# Mixer_Console_PCB.net
KiCad netlist of a schematic drawn in EAGLE
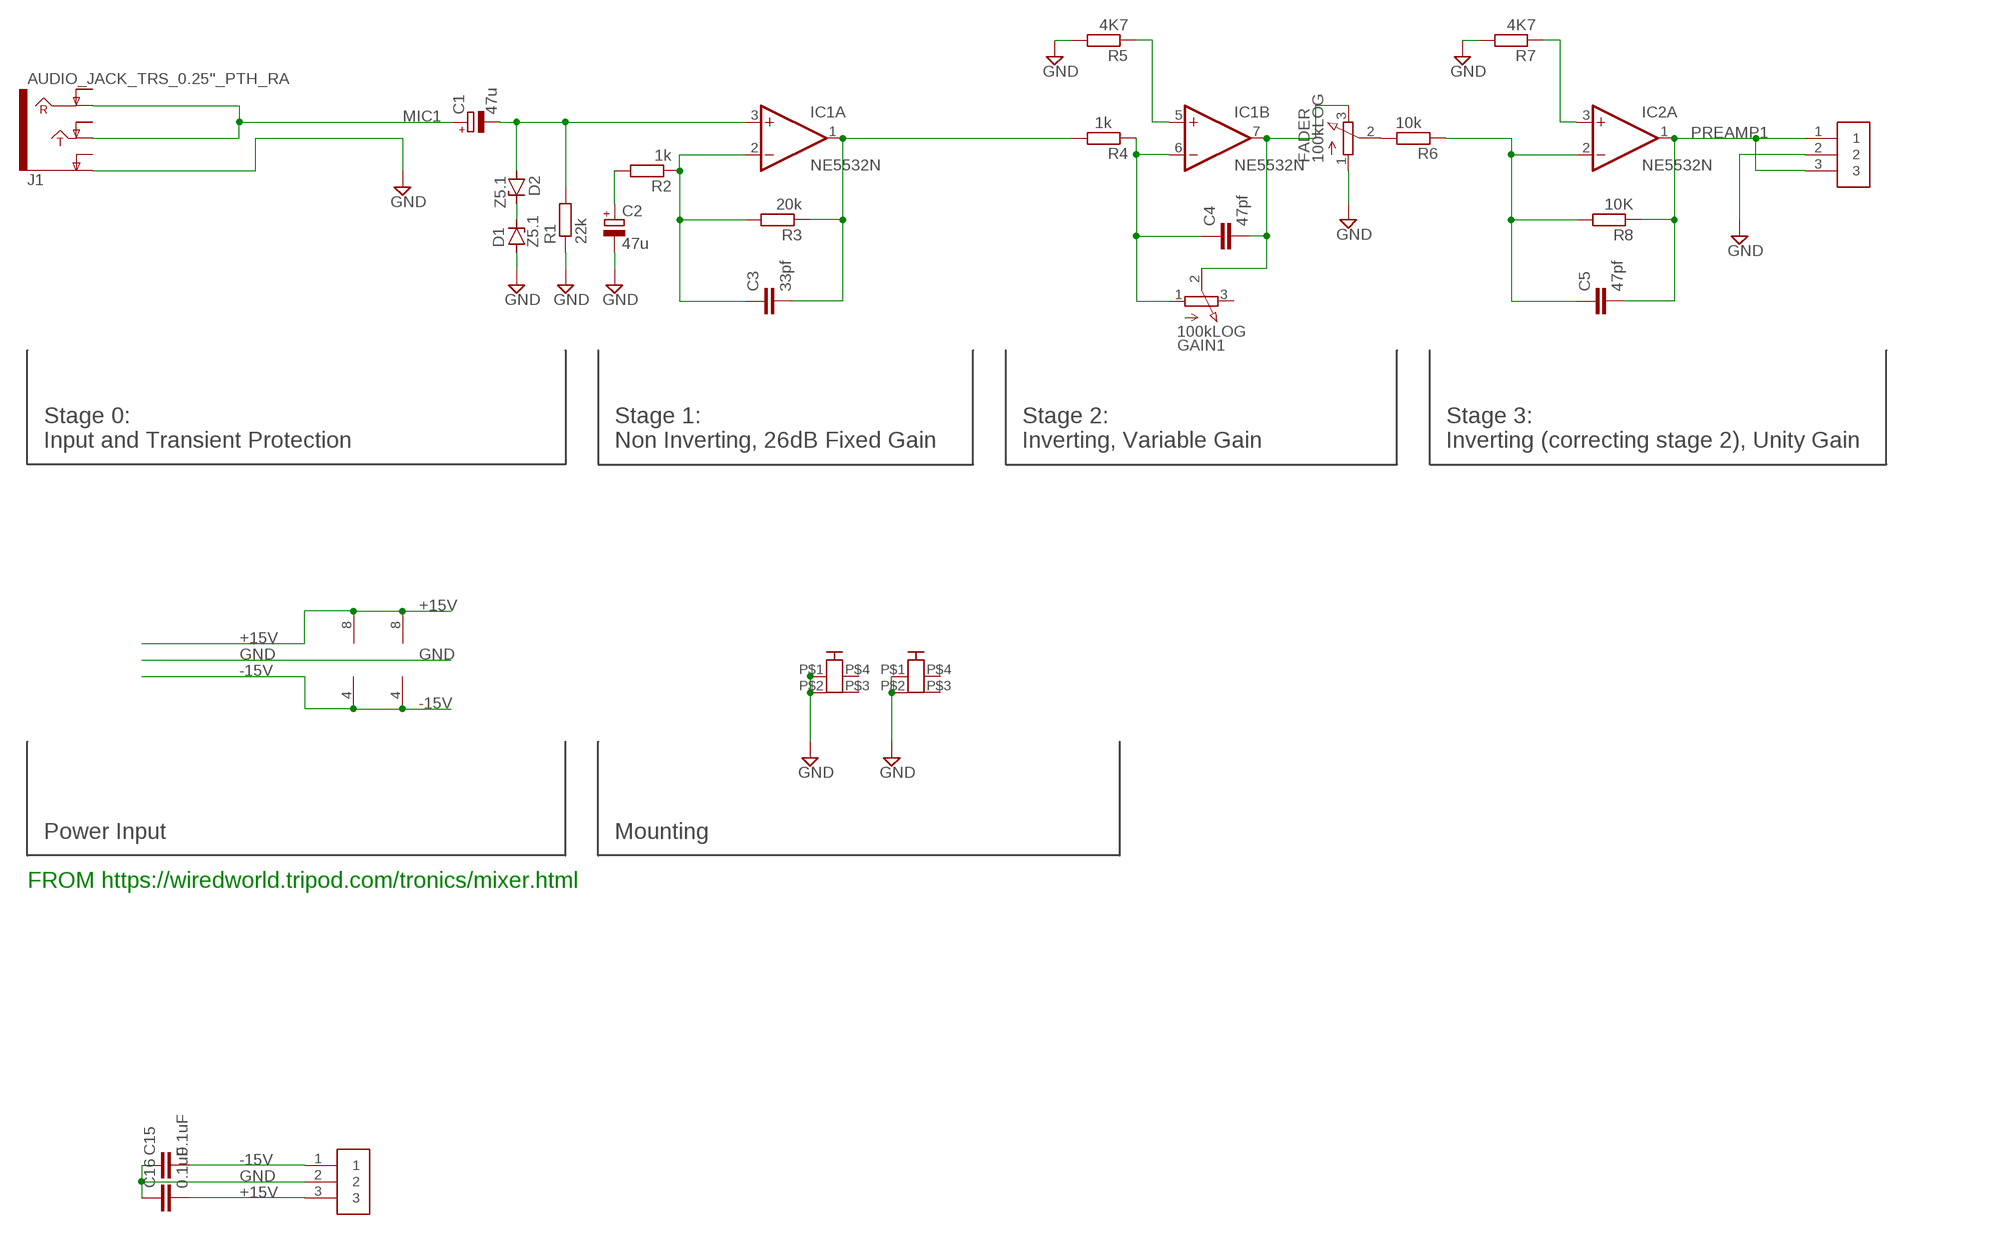
[diagram p0: schematic, sheet 1]
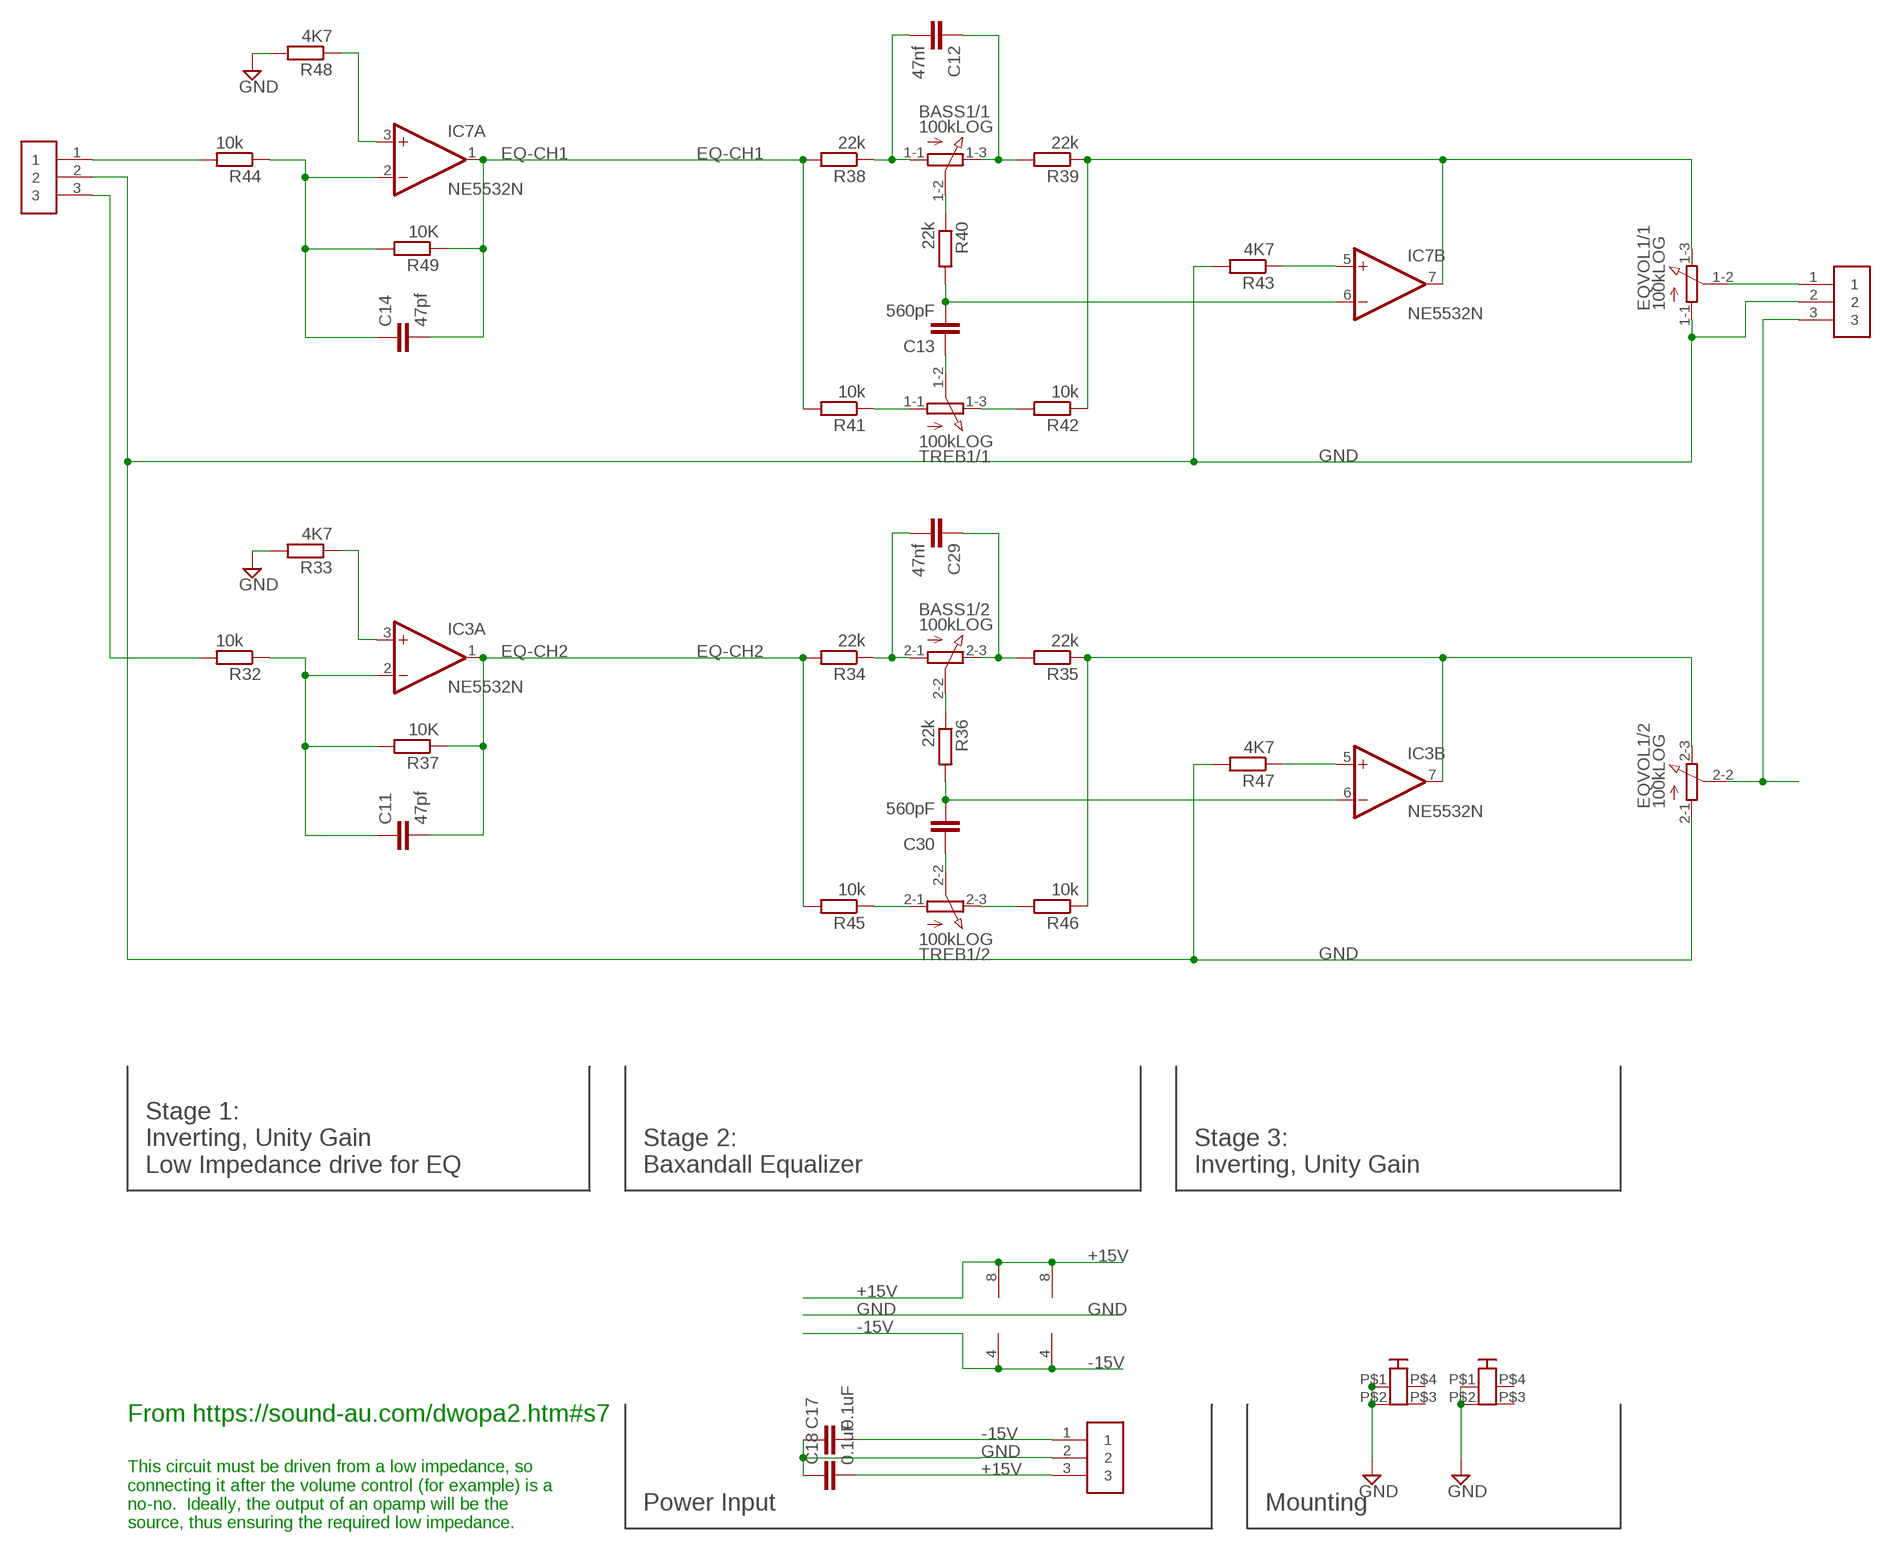
[diagram p1: schematic, sheet 2]
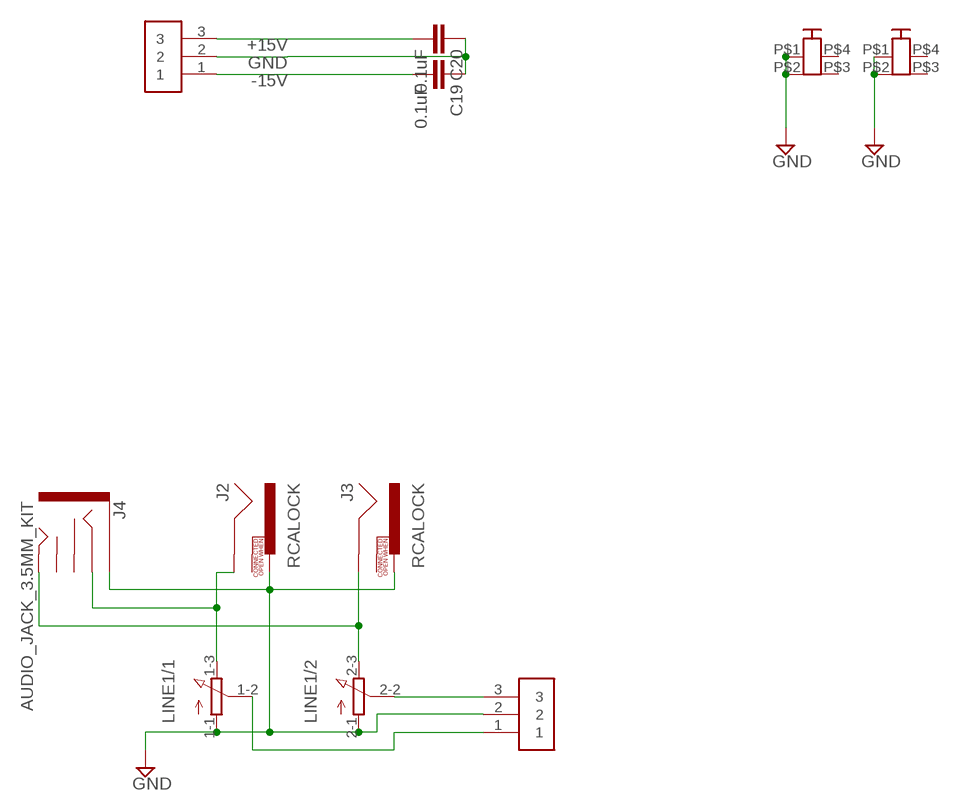
[diagram p2: schematic, sheet 3]
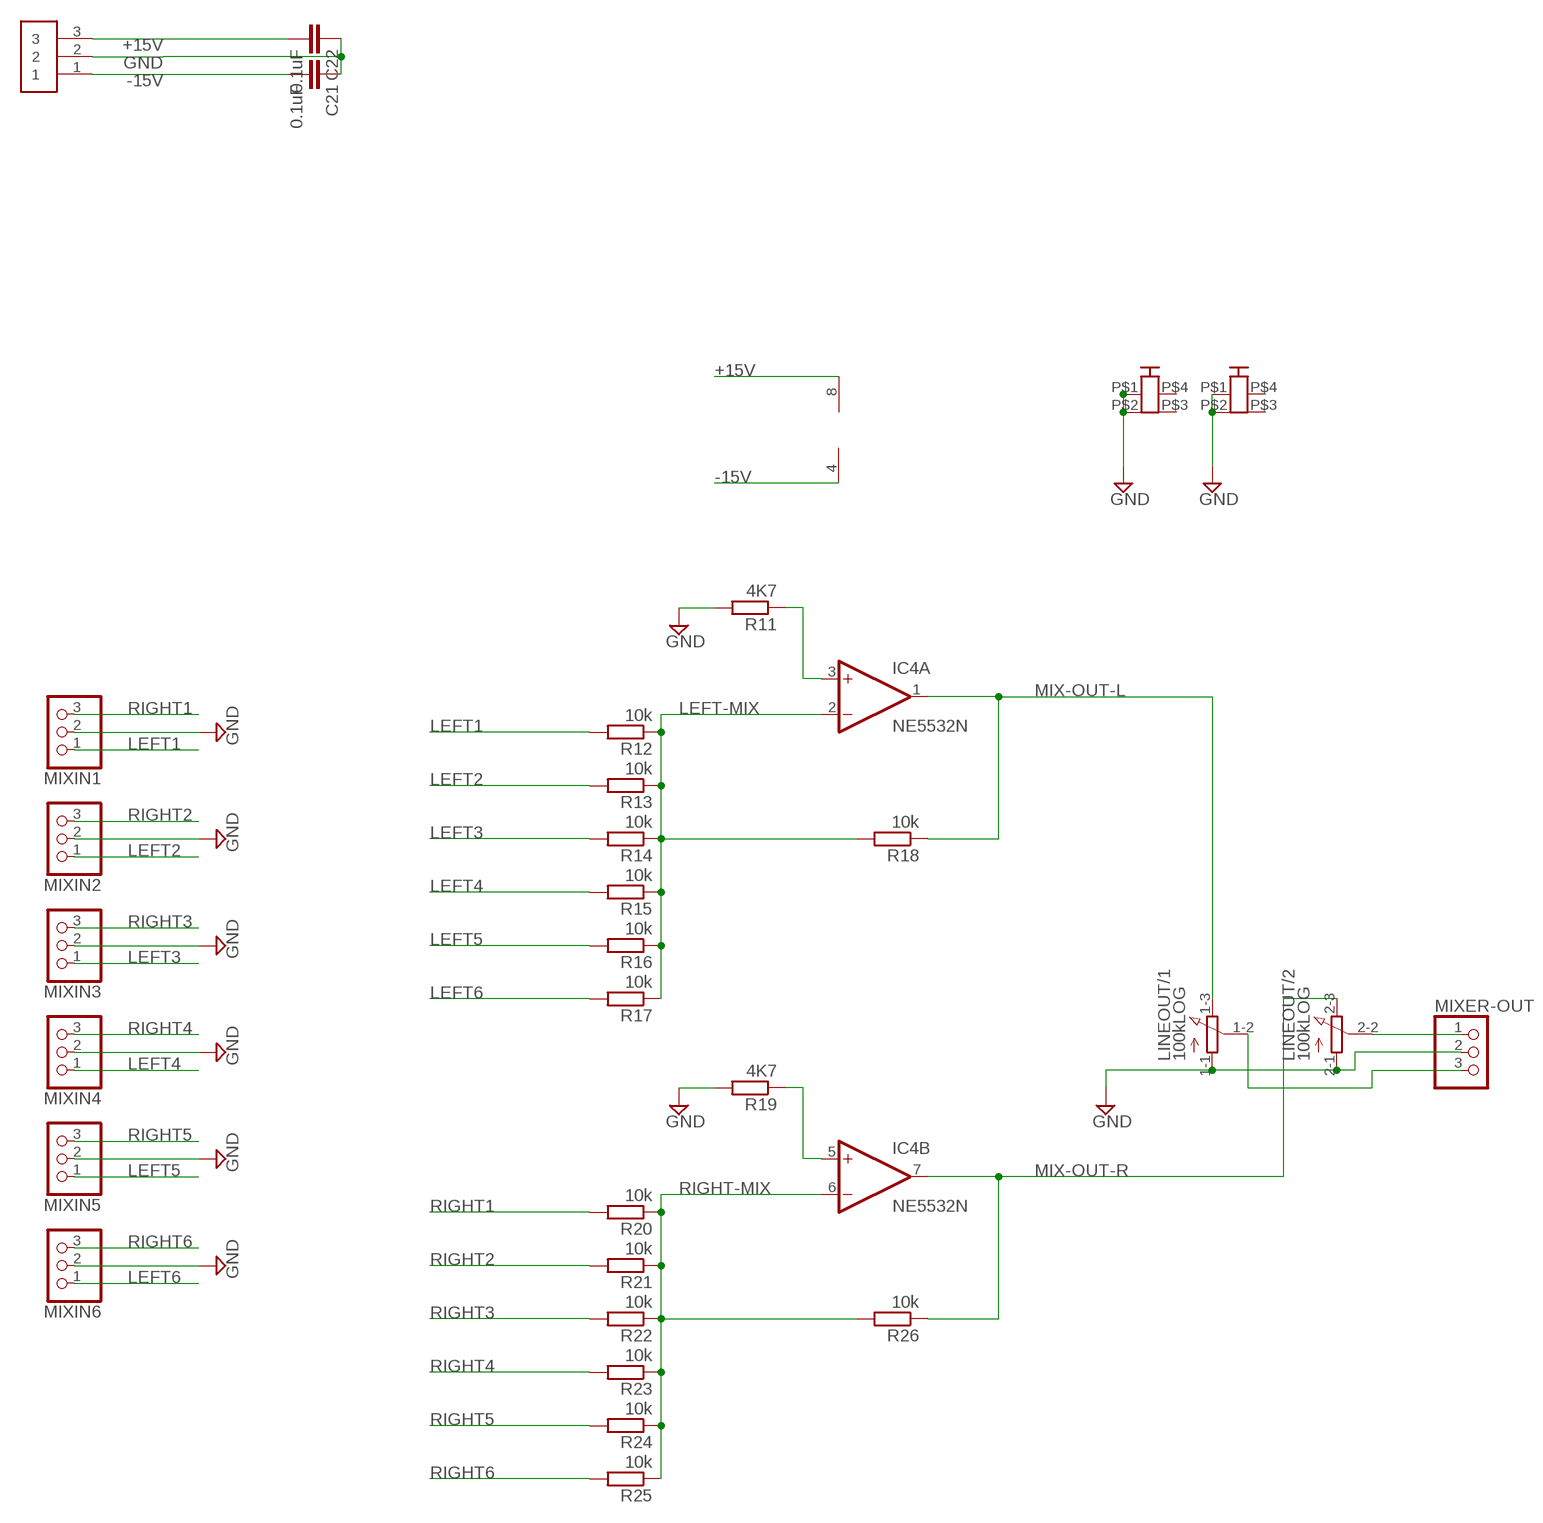
[diagram p3: schematic, sheet 4]
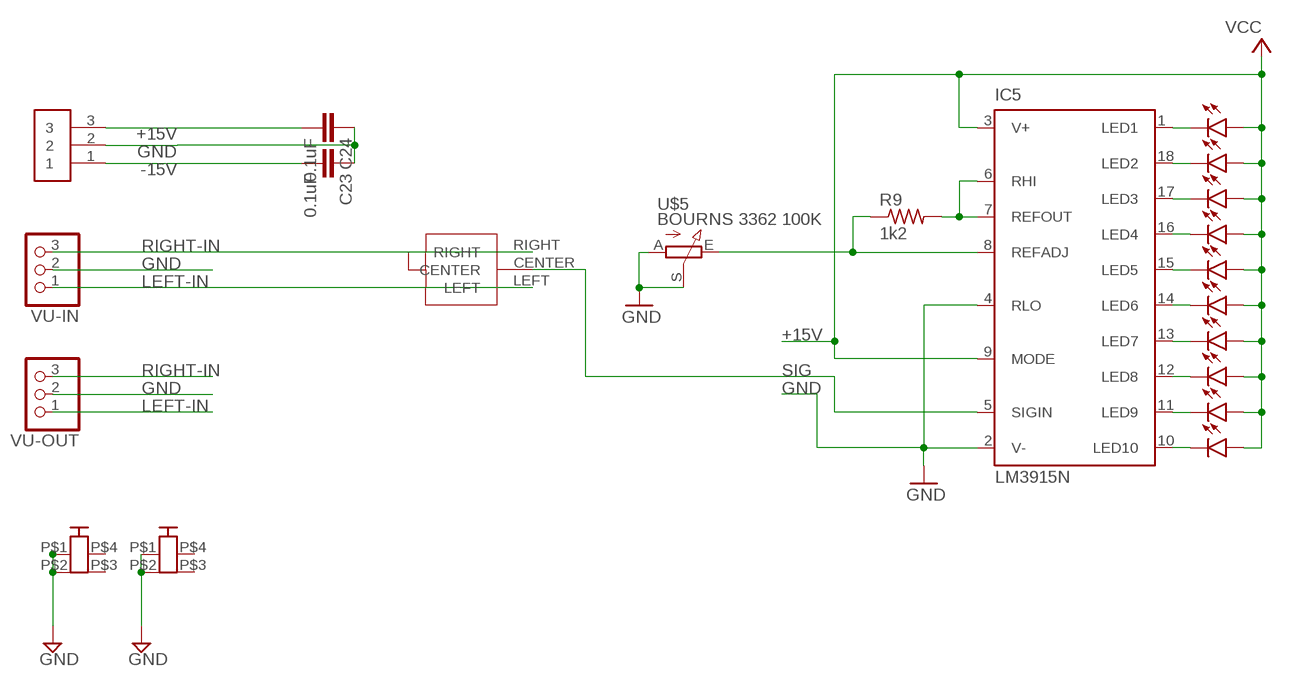
[diagram p4: schematic, sheet 5]
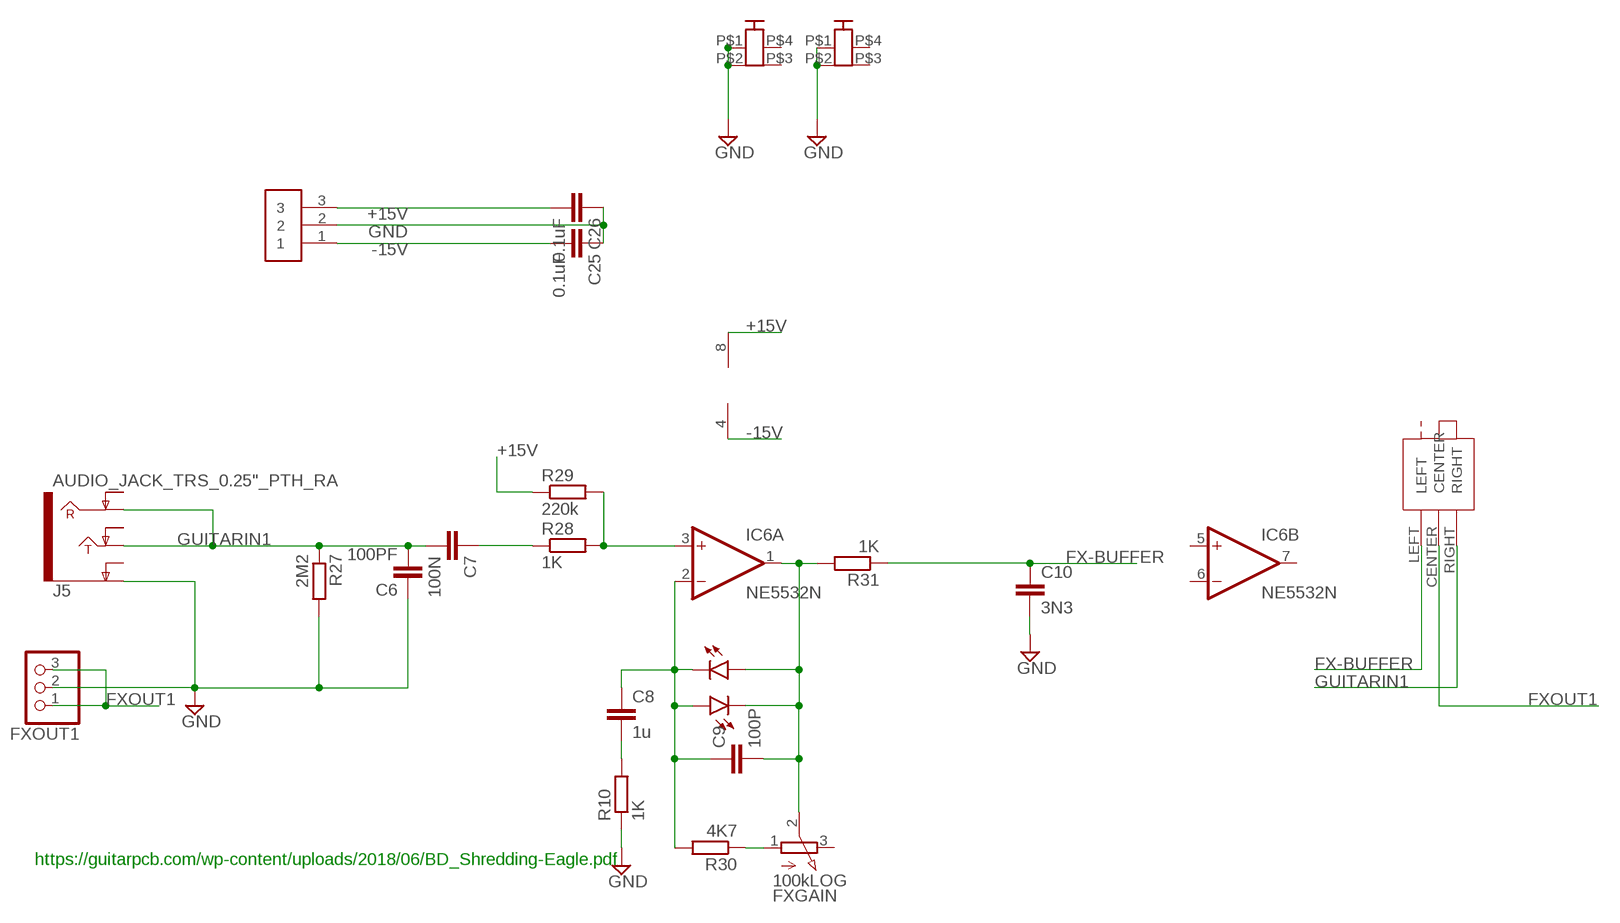
[diagram p5: schematic, sheet 6]

(export (version "E")
  (design (tool "Eeschema 10.0.6"))
  (components
    (comp (ref "BASS1")
      (value "100kLOG")
      (footprint "eagle-import:3RP_1610G")
      (fields (field (name "SPICEPREFIX") "J"))
      (libsource (lib "eagle-import") (part "3RP/1610G"))
    )
    (comp (ref "C11")
      (value "47pf")
      (footprint "eagle-import:C2.5-2")
      (libsource (lib "eagle-import") (part "C2.5/2"))
    )
    (comp (ref "C12")
      (value "47nf")
      (footprint "eagle-import:C2.5-2")
      (libsource (lib "eagle-import") (part "C2.5/2"))
    )
    (comp (ref "C13")
      (value "560pF")
      (footprint "eagle-import:C2.5-2")
      (libsource (lib "eagle-import") (part "C2.5/2"))
    )
    (comp (ref "C14")
      (value "47pf")
      (footprint "eagle-import:C2.5-2")
      (libsource (lib "eagle-import") (part "C2.5/2"))
    )
    (comp (ref "C17")
      (value "0.1uF")
      (footprint "eagle-import:C2.5-2")
      (libsource (lib "eagle-import") (part "C2.5/2"))
    )
    (comp (ref "C18")
      (value "0.1uF")
      (footprint "eagle-import:C2.5-2")
      (libsource (lib "eagle-import") (part "C2.5/2"))
    )
    (comp (ref "C29")
      (value "47nf")
      (footprint "eagle-import:C2.5-2")
      (libsource (lib "eagle-import") (part "C2.5/2"))
    )
    (comp (ref "C30")
      (value "560pF")
      (footprint "eagle-import:C2.5-2")
      (libsource (lib "eagle-import") (part "C2.5/2"))
    )
    (comp (ref "CON1")
      (value "PCB-2M3")
      (footprint "eagle-import:PCB2-M3")
      (libsource (lib "eagle-import") (part "PCB-2M3"))
    )
    (comp (ref "CON2")
      (value "PCB-2M3")
      (footprint "eagle-import:PCB2-M3")
      (libsource (lib "eagle-import") (part "PCB-2M3"))
    )
    (comp (ref "EQIN")
      (value "Phoenix Pluggable 3.81mm 3 way")
      (footprint "eagle-import:3.81MM-3WAY-PLUGGABLE-SCREW")
      (libsource (lib "eagle-import") (part "CONNECTOR-M3"))
    )
    (comp (ref "EQOUT")
      (value "Phoenix Pluggable 3.81mm 3 way")
      (footprint "eagle-import:3.81MM-3WAY-PLUGGABLE-SCREW")
      (libsource (lib "eagle-import") (part "CONNECTOR-M3"))
    )
    (comp (ref "EQVOL1")
      (value "100kLOG")
      (footprint "eagle-import:3RP_1610G")
      (fields (field (name "SPICEPREFIX") "J"))
      (libsource (lib "eagle-import") (part "3RP/1610G"))
    )
    (comp (ref "IC3")
      (value "NE5532N")
      (footprint "eagle-import:DIL08")
      (libsource (lib "eagle-import") (part "NE5532N"))
    )
    (comp (ref "IC7")
      (value "NE5532N")
      (footprint "eagle-import:DIL08")
      (libsource (lib "eagle-import") (part "NE5532N"))
    )
    (comp (ref "PWRIN1")
      (value "Phoenix Pluggable 3.81mm 3 way")
      (footprint "eagle-import:3.81MM-3WAY-PLUGGABLE-SCREW")
      (libsource (lib "eagle-import") (part "CONNECTOR-M3"))
    )
    (comp (ref "R32")
      (value "10k")
      (footprint "eagle-import:0204_7")
      (libsource (lib "eagle-import") (part "R-EU_0204/7"))
    )
    (comp (ref "R33")
      (value "4K7")
      (footprint "eagle-import:0204_7")
      (libsource (lib "eagle-import") (part "R-EU_0204/7"))
    )
    (comp (ref "R34")
      (value "22k")
      (footprint "eagle-import:0204_7")
      (libsource (lib "eagle-import") (part "R-EU_0204/7"))
    )
    (comp (ref "R35")
      (value "22k")
      (footprint "eagle-import:0204_7")
      (libsource (lib "eagle-import") (part "R-EU_0204/7"))
    )
    (comp (ref "R36")
      (value "22k")
      (footprint "eagle-import:0204_7")
      (libsource (lib "eagle-import") (part "R-EU_0204/7"))
    )
    (comp (ref "R37")
      (value "10K")
      (footprint "eagle-import:0204_7")
      (libsource (lib "eagle-import") (part "R-EU_0204/7"))
    )
    (comp (ref "R38")
      (value "22k")
      (footprint "eagle-import:0204_7")
      (libsource (lib "eagle-import") (part "R-EU_0204/7"))
    )
    (comp (ref "R39")
      (value "22k")
      (footprint "eagle-import:0204_7")
      (libsource (lib "eagle-import") (part "R-EU_0204/7"))
    )
    (comp (ref "R40")
      (value "22k")
      (footprint "eagle-import:0204_7")
      (libsource (lib "eagle-import") (part "R-EU_0204/7"))
    )
    (comp (ref "R41")
      (value "10k")
      (footprint "eagle-import:0204_7")
      (libsource (lib "eagle-import") (part "R-EU_0204/7"))
    )
    (comp (ref "R42")
      (value "10k")
      (footprint "eagle-import:0204_7")
      (libsource (lib "eagle-import") (part "R-EU_0204/7"))
    )
    (comp (ref "R43")
      (value "4K7")
      (footprint "eagle-import:0204_7")
      (libsource (lib "eagle-import") (part "R-EU_0204/7"))
    )
    (comp (ref "R44")
      (value "10k")
      (footprint "eagle-import:0204_7")
      (libsource (lib "eagle-import") (part "R-EU_0204/7"))
    )
    (comp (ref "R45")
      (value "10k")
      (footprint "eagle-import:0204_7")
      (libsource (lib "eagle-import") (part "R-EU_0204/7"))
    )
    (comp (ref "R46")
      (value "10k")
      (footprint "eagle-import:0204_7")
      (libsource (lib "eagle-import") (part "R-EU_0204/7"))
    )
    (comp (ref "R47")
      (value "4K7")
      (footprint "eagle-import:0204_7")
      (libsource (lib "eagle-import") (part "R-EU_0204/7"))
    )
    (comp (ref "R48")
      (value "4K7")
      (footprint "eagle-import:0204_7")
      (libsource (lib "eagle-import") (part "R-EU_0204/7"))
    )
    (comp (ref "R49")
      (value "10K")
      (footprint "eagle-import:0204_7")
      (libsource (lib "eagle-import") (part "R-EU_0204/7"))
    )
    (comp (ref "TREB1")
      (value "100kLOG")
      (footprint "eagle-import:3RP_1610G")
      (fields (field (name "SPICEPREFIX") "J"))
      (libsource (lib "eagle-import") (part "3RP/1610G"))
    )
    (comp (ref "C6")
      (value "100PF")
      (footprint "eagle-import:C2.5-2")
      (libsource (lib "eagle-import") (part "C2.5/2"))
    )
    (comp (ref "C7")
      (value "100N")
      (footprint "eagle-import:C2.5-2")
      (libsource (lib "eagle-import") (part "C2.5/2"))
    )
    (comp (ref "C8")
      (value "1u")
      (footprint "eagle-import:C2.5-2")
      (libsource (lib "eagle-import") (part "C2.5/2"))
    )
    (comp (ref "C9")
      (value "100P")
      (footprint "eagle-import:C2.5-2")
      (libsource (lib "eagle-import") (part "C2.5/2"))
    )
    (comp (ref "C10")
      (value "3N3")
      (footprint "eagle-import:C2.5-2")
      (libsource (lib "eagle-import") (part "C2.5/2"))
    )
    (comp (ref "C25")
      (value "0.1uF")
      (footprint "eagle-import:C2.5-2")
      (libsource (lib "eagle-import") (part "C2.5/2"))
    )
    (comp (ref "C26")
      (value "0.1uF")
      (footprint "eagle-import:C2.5-2")
      (libsource (lib "eagle-import") (part "C2.5/2"))
    )
    (comp (ref "CON9")
      (value "PCB-2M3")
      (footprint "eagle-import:PCB2-M3")
      (libsource (lib "eagle-import") (part "PCB-2M3"))
    )
    (comp (ref "CON10")
      (value "PCB-2M3")
      (footprint "eagle-import:PCB2-M3")
      (libsource (lib "eagle-import") (part "PCB-2M3"))
    )
    (comp (ref "FXGAIN")
      (value "100kLOG")
      (footprint "eagle-import:3RP_1610N")
      (libsource (lib "eagle-import") (part "3RP/1610N"))
    )
    (comp (ref "FXOUT1")
      (value "PINHD-1X3/90")
      (footprint "eagle-import:1X03_90")
      (libsource (lib "eagle-import") (part "PINHD-1X3/90"))
    )
    (comp (ref "IC6")
      (value "NE5532N")
      (footprint "eagle-import:DIL08")
      (libsource (lib "eagle-import") (part "NE5532N"))
    )
    (comp (ref "J5")
      (value "AUDIO_JACK_TRS_0.25\"_PTH_RA")
      (footprint "eagle-import:AUDIO_JACK_0.25__TRS_PTH_RA")
      (libsource (lib "eagle-import") (part "AUDIO_JACK_TRS_0.25{dblquote}_PTH_RA"))
    )
    (comp (ref "LED11")
      (value "LED3MM")
      (footprint "eagle-import:LED3MM")
      (libsource (lib "eagle-import") (part "LED3MM"))
    )
    (comp (ref "LED12")
      (value "LED3MM")
      (footprint "eagle-import:LED3MM")
      (libsource (lib "eagle-import") (part "LED3MM"))
    )
    (comp (ref "PWRIN5")
      (value "Phoenix Pluggable 3.81mm 3 way")
      (footprint "eagle-import:3.81MM-3WAY-PLUGGABLE-SCREW")
      (libsource (lib "eagle-import") (part "CONNECTOR-M3"))
    )
    (comp (ref "R10")
      (value "1K")
      (footprint "eagle-import:0204_7")
      (libsource (lib "eagle-import") (part "R-EU_0204/7"))
    )
    (comp (ref "R27")
      (value "2M2")
      (footprint "eagle-import:0204_7")
      (libsource (lib "eagle-import") (part "R-EU_0204/7"))
    )
    (comp (ref "R28")
      (value "1K")
      (footprint "eagle-import:0204_7")
      (libsource (lib "eagle-import") (part "R-EU_0204/7"))
    )
    (comp (ref "R29")
      (value "220k")
      (footprint "eagle-import:0204_7")
      (libsource (lib "eagle-import") (part "R-EU_0204/7"))
    )
    (comp (ref "R30")
      (value "4K7")
      (footprint "eagle-import:0204_7")
      (libsource (lib "eagle-import") (part "R-EU_0204/7"))
    )
    (comp (ref "R31")
      (value "1K")
      (footprint "eagle-import:0204_7")
      (libsource (lib "eagle-import") (part "R-EU_0204/7"))
    )
    (comp (ref "U$1")
      (value "XKBENTERPRISESS-12D11G5R")
      (footprint "eagle-import:XKBENTERPRISESS-12D11G5R")
      (libsource (lib "eagle-import") (part "XKBENTERPRISESS-12D11G5R"))
    )
    (comp (ref "C1")
      (value "47u")
      (footprint "eagle-import:E5-6")
      (libsource (lib "eagle-import") (part "CPOL-EUE5-6"))
    )
    (comp (ref "C2")
      (value "47u")
      (footprint "eagle-import:E5-6")
      (libsource (lib "eagle-import") (part "CPOL-EUE5-6"))
    )
    (comp (ref "C3")
      (value "33pf")
      (footprint "eagle-import:C2.5-2")
      (libsource (lib "eagle-import") (part "C2.5/2"))
    )
    (comp (ref "C4")
      (value "47pf")
      (footprint "eagle-import:C2.5-2")
      (libsource (lib "eagle-import") (part "C2.5/2"))
    )
    (comp (ref "C5")
      (value "47pf")
      (footprint "eagle-import:C2.5-2")
      (libsource (lib "eagle-import") (part "C2.5/2"))
    )
    (comp (ref "C15")
      (value "0.1uF")
      (footprint "eagle-import:C2.5-2")
      (libsource (lib "eagle-import") (part "C2.5/2"))
    )
    (comp (ref "C16")
      (value "0.1uF")
      (footprint "eagle-import:C2.5-2")
      (libsource (lib "eagle-import") (part "C2.5/2"))
    )
    (comp (ref "CON11")
      (value "PCB-2M3")
      (footprint "eagle-import:PCB2-M3")
      (libsource (lib "eagle-import") (part "PCB-2M3"))
    )
    (comp (ref "CON12")
      (value "PCB-2M3")
      (footprint "eagle-import:PCB2-M3")
      (libsource (lib "eagle-import") (part "PCB-2M3"))
    )
    (comp (ref "D1")
      (value "Z5.1")
      (footprint "eagle-import:DO34Z7")
      (libsource (lib "eagle-import") (part "ZENER-DIODEDO34-7"))
    )
    (comp (ref "D2")
      (value "Z5.1")
      (footprint "eagle-import:DO34Z7")
      (libsource (lib "eagle-import") (part "ZENER-DIODEDO34-7"))
    )
    (comp (ref "FADER")
      (value "100kLOG")
      (footprint "eagle-import:3RP_1610N")
      (libsource (lib "eagle-import") (part "3RP/1610N"))
    )
    (comp (ref "GAIN1")
      (value "100kLOG")
      (footprint "eagle-import:3RP_1610N")
      (libsource (lib "eagle-import") (part "3RP/1610N"))
    )
    (comp (ref "IC1")
      (value "NE5532N")
      (footprint "eagle-import:DIL08")
      (libsource (lib "eagle-import") (part "NE5532N"))
    )
    (comp (ref "IC2")
      (value "NE5532N")
      (footprint "eagle-import:DIL08")
      (libsource (lib "eagle-import") (part "NE5532N"))
    )
    (comp (ref "J1")
      (value "AUDIO_JACK_TRS_0.25\"_PTH_RA")
      (footprint "eagle-import:AUDIO_JACK_0.25__TRS_PTH_RA")
      (libsource (lib "eagle-import") (part "AUDIO_JACK_TRS_0.25{dblquote}_PTH_RA"))
    )
    (comp (ref "PREAMPOUT")
      (value "Phoenix Pluggable 3.81mm 3 way")
      (footprint "eagle-import:3.81MM-3WAY-PLUGGABLE-SCREW")
      (libsource (lib "eagle-import") (part "CONNECTOR-M3"))
    )
    (comp (ref "PWRIN")
      (value "Phoenix Pluggable 3.81mm 3 way")
      (footprint "eagle-import:3.81MM-3WAY-PLUGGABLE-SCREW")
      (libsource (lib "eagle-import") (part "CONNECTOR-M3"))
    )
    (comp (ref "R1")
      (value "22k")
      (footprint "eagle-import:0204_7")
      (libsource (lib "eagle-import") (part "R-EU_0204/7"))
    )
    (comp (ref "R2")
      (value "1k")
      (footprint "eagle-import:0204_7")
      (libsource (lib "eagle-import") (part "R-EU_0204/7"))
    )
    (comp (ref "R3")
      (value "20k")
      (footprint "eagle-import:0204_7")
      (libsource (lib "eagle-import") (part "R-EU_0204/7"))
    )
    (comp (ref "R4")
      (value "1k")
      (footprint "eagle-import:0204_7")
      (libsource (lib "eagle-import") (part "R-EU_0204/7"))
    )
    (comp (ref "R5")
      (value "4K7")
      (footprint "eagle-import:0204_7")
      (libsource (lib "eagle-import") (part "R-EU_0204/7"))
    )
    (comp (ref "R6")
      (value "10k")
      (footprint "eagle-import:0204_7")
      (libsource (lib "eagle-import") (part "R-EU_0204/7"))
    )
    (comp (ref "R7")
      (value "4K7")
      (footprint "eagle-import:0204_7")
      (libsource (lib "eagle-import") (part "R-EU_0204/7"))
    )
    (comp (ref "R8")
      (value "10K")
      (footprint "eagle-import:0204_7")
      (libsource (lib "eagle-import") (part "R-EU_0204/7"))
    )
    (comp (ref "C21")
      (value "0.1uF")
      (footprint "eagle-import:C2.5-2")
      (libsource (lib "eagle-import") (part "C2.5/2"))
    )
    (comp (ref "C22")
      (value "0.1uF")
      (footprint "eagle-import:C2.5-2")
      (libsource (lib "eagle-import") (part "C2.5/2"))
    )
    (comp (ref "CON5")
      (value "PCB-2M3")
      (footprint "eagle-import:PCB2-M3")
      (libsource (lib "eagle-import") (part "PCB-2M3"))
    )
    (comp (ref "CON6")
      (value "PCB-2M3")
      (footprint "eagle-import:PCB2-M3")
      (libsource (lib "eagle-import") (part "PCB-2M3"))
    )
    (comp (ref "IC4")
      (value "NE5532N")
      (footprint "eagle-import:DIL08")
      (libsource (lib "eagle-import") (part "NE5532N"))
    )
    (comp (ref "LINEOUT")
      (value "100kLOG")
      (footprint "eagle-import:3RP_1610G")
      (libsource (lib "eagle-import") (part "3RP/1610G"))
    )
    (comp (ref "MIXER-OUT")
      (value "PINHD-1X3/90")
      (footprint "eagle-import:1X03_90")
      (libsource (lib "eagle-import") (part "PINHD-1X3/90"))
    )
    (comp (ref "MIXIN1")
      (value "PINHD-1X3/90")
      (footprint "eagle-import:1X03_90")
      (libsource (lib "eagle-import") (part "PINHD-1X3/90"))
    )
    (comp (ref "MIXIN2")
      (value "PINHD-1X3/90")
      (footprint "eagle-import:1X03_90")
      (libsource (lib "eagle-import") (part "PINHD-1X3/90"))
    )
    (comp (ref "MIXIN3")
      (value "PINHD-1X3/90")
      (footprint "eagle-import:1X03_90")
      (libsource (lib "eagle-import") (part "PINHD-1X3/90"))
    )
    (comp (ref "MIXIN4")
      (value "PINHD-1X3/90")
      (footprint "eagle-import:1X03_90")
      (libsource (lib "eagle-import") (part "PINHD-1X3/90"))
    )
    (comp (ref "MIXIN5")
      (value "PINHD-1X3/90")
      (footprint "eagle-import:1X03_90")
      (libsource (lib "eagle-import") (part "PINHD-1X3/90"))
    )
    (comp (ref "MIXIN6")
      (value "PINHD-1X3/90")
      (footprint "eagle-import:1X03_90")
      (libsource (lib "eagle-import") (part "PINHD-1X3/90"))
    )
    (comp (ref "PWRIN3")
      (value "Phoenix Pluggable 3.81mm 3 way")
      (footprint "eagle-import:3.81MM-3WAY-PLUGGABLE-SCREW")
      (libsource (lib "eagle-import") (part "CONNECTOR-M3"))
    )
    (comp (ref "R11")
      (value "4K7")
      (footprint "eagle-import:0204_7")
      (libsource (lib "eagle-import") (part "R-EU_0204/7"))
    )
    (comp (ref "R12")
      (value "10k")
      (footprint "eagle-import:0204_7")
      (libsource (lib "eagle-import") (part "R-EU_0204/7"))
    )
    (comp (ref "R13")
      (value "10k")
      (footprint "eagle-import:0204_7")
      (libsource (lib "eagle-import") (part "R-EU_0204/7"))
    )
    (comp (ref "R14")
      (value "10k")
      (footprint "eagle-import:0204_7")
      (libsource (lib "eagle-import") (part "R-EU_0204/7"))
    )
    (comp (ref "R15")
      (value "10k")
      (footprint "eagle-import:0204_7")
      (libsource (lib "eagle-import") (part "R-EU_0204/7"))
    )
    (comp (ref "R16")
      (value "10k")
      (footprint "eagle-import:0204_7")
      (libsource (lib "eagle-import") (part "R-EU_0204/7"))
    )
    (comp (ref "R17")
      (value "10k")
      (footprint "eagle-import:0204_7")
      (libsource (lib "eagle-import") (part "R-EU_0204/7"))
    )
    (comp (ref "R18")
      (value "10k")
      (footprint "eagle-import:0204_7")
      (libsource (lib "eagle-import") (part "R-EU_0204/7"))
    )
    (comp (ref "R19")
      (value "4K7")
      (footprint "eagle-import:0204_7")
      (libsource (lib "eagle-import") (part "R-EU_0204/7"))
    )
    (comp (ref "R20")
      (value "10k")
      (footprint "eagle-import:0204_7")
      (libsource (lib "eagle-import") (part "R-EU_0204/7"))
    )
    (comp (ref "R21")
      (value "10k")
      (footprint "eagle-import:0204_7")
      (libsource (lib "eagle-import") (part "R-EU_0204/7"))
    )
    (comp (ref "R22")
      (value "10k")
      (footprint "eagle-import:0204_7")
      (libsource (lib "eagle-import") (part "R-EU_0204/7"))
    )
    (comp (ref "R23")
      (value "10k")
      (footprint "eagle-import:0204_7")
      (libsource (lib "eagle-import") (part "R-EU_0204/7"))
    )
    (comp (ref "R24")
      (value "10k")
      (footprint "eagle-import:0204_7")
      (libsource (lib "eagle-import") (part "R-EU_0204/7"))
    )
    (comp (ref "R25")
      (value "10k")
      (footprint "eagle-import:0204_7")
      (libsource (lib "eagle-import") (part "R-EU_0204/7"))
    )
    (comp (ref "R26")
      (value "10k")
      (footprint "eagle-import:0204_7")
      (libsource (lib "eagle-import") (part "R-EU_0204/7"))
    )
    (comp (ref "C23")
      (value "0.1uF")
      (footprint "eagle-import:C2.5-2")
      (libsource (lib "eagle-import") (part "C2.5/2"))
    )
    (comp (ref "C24")
      (value "0.1uF")
      (footprint "eagle-import:C2.5-2")
      (libsource (lib "eagle-import") (part "C2.5/2"))
    )
    (comp (ref "CON7")
      (value "PCB-2M3")
      (footprint "eagle-import:PCB2-M3")
      (libsource (lib "eagle-import") (part "PCB-2M3"))
    )
    (comp (ref "CON8")
      (value "PCB-2M3")
      (footprint "eagle-import:PCB2-M3")
      (libsource (lib "eagle-import") (part "PCB-2M3"))
    )
    (comp (ref "IC5")
      (value "LM3915N")
      (footprint "eagle-import:DIL18")
      (libsource (lib "eagle-import") (part "LM391N5"))
    )
    (comp (ref "LED1")
      (value "LED3MM")
      (footprint "eagle-import:LED3MM")
      (libsource (lib "eagle-import") (part "LED3MM"))
    )
    (comp (ref "LED2")
      (value "LED3MM")
      (footprint "eagle-import:LED3MM")
      (libsource (lib "eagle-import") (part "LED3MM"))
    )
    (comp (ref "LED3")
      (value "LED3MM")
      (footprint "eagle-import:LED3MM")
      (libsource (lib "eagle-import") (part "LED3MM"))
    )
    (comp (ref "LED4")
      (value "LED3MM")
      (footprint "eagle-import:LED3MM")
      (libsource (lib "eagle-import") (part "LED3MM"))
    )
    (comp (ref "LED5")
      (value "LED3MM")
      (footprint "eagle-import:LED3MM")
      (libsource (lib "eagle-import") (part "LED3MM"))
    )
    (comp (ref "LED6")
      (value "LED3MM")
      (footprint "eagle-import:LED3MM")
      (libsource (lib "eagle-import") (part "LED3MM"))
    )
    (comp (ref "LED7")
      (value "LED3MM")
      (footprint "eagle-import:LED3MM")
      (libsource (lib "eagle-import") (part "LED3MM"))
    )
    (comp (ref "LED8")
      (value "LED3MM")
      (footprint "eagle-import:LED3MM")
      (libsource (lib "eagle-import") (part "LED3MM"))
    )
    (comp (ref "LED9")
      (value "LED3MM")
      (footprint "eagle-import:LED3MM")
      (libsource (lib "eagle-import") (part "LED3MM"))
    )
    (comp (ref "LED10")
      (value "LED3MM")
      (footprint "eagle-import:LED3MM")
      (libsource (lib "eagle-import") (part "LED3MM"))
    )
    (comp (ref "PWRIN4")
      (value "Phoenix Pluggable 3.81mm 3 way")
      (footprint "eagle-import:3.81MM-3WAY-PLUGGABLE-SCREW")
      (libsource (lib "eagle-import") (part "CONNECTOR-M3"))
    )
    (comp (ref "R9")
      (value "1k2")
      (footprint "eagle-import:0207_10")
      (libsource (lib "eagle-import") (part "R-US_0207/10"))
    )
    (comp (ref "U$2")
      (value "XKBENTERPRISESS-12D11G5R")
      (footprint "eagle-import:XKBENTERPRISESS-12D11G5R")
      (libsource (lib "eagle-import") (part "XKBENTERPRISESS-12D11G5R"))
    )
    (comp (ref "U$5")
      (value "BOURNS 3362 100K")
      (footprint "eagle-import:POT_B64W")
      (libsource (lib "eagle-import") (part "POTVERTICAL"))
    )
    (comp (ref "VU-IN")
      (value "PINHD-1X3/90")
      (footprint "eagle-import:1X03_90")
      (libsource (lib "eagle-import") (part "PINHD-1X3/90"))
    )
    (comp (ref "VU-OUT")
      (value "PINHD-1X3/90")
      (footprint "eagle-import:1X03_90")
      (libsource (lib "eagle-import") (part "PINHD-1X3/90"))
    )
    (comp (ref "C19")
      (value "0.1uF")
      (footprint "eagle-import:C2.5-2")
      (libsource (lib "eagle-import") (part "C2.5/2"))
    )
    (comp (ref "C20")
      (value "0.1uF")
      (footprint "eagle-import:C2.5-2")
      (libsource (lib "eagle-import") (part "C2.5/2"))
    )
    (comp (ref "CON3")
      (value "PCB-2M3")
      (footprint "eagle-import:PCB2-M3")
      (libsource (lib "eagle-import") (part "PCB-2M3"))
    )
    (comp (ref "CON4")
      (value "PCB-2M3")
      (footprint "eagle-import:PCB2-M3")
      (libsource (lib "eagle-import") (part "PCB-2M3"))
    )
    (comp (ref "J2")
      (value "RCALOCK")
      (footprint "eagle-import:RCA_LOCK")
      (libsource (lib "eagle-import") (part "RCALOCK"))
    )
    (comp (ref "J3")
      (value "RCALOCK")
      (footprint "eagle-import:RCA_LOCK")
      (libsource (lib "eagle-import") (part "RCALOCK"))
    )
    (comp (ref "J4")
      (value "AUDIO_JACK_3.5MM_KIT")
      (footprint "eagle-import:AUDIO-JACK-KIT")
      (libsource (lib "eagle-import") (part "AUDIO_JACK_3.5MM_KIT"))
    )
    (comp (ref "LINE1")
      (value "3RP/1610G")
      (footprint "eagle-import:3RP_1610G")
      (libsource (lib "eagle-import") (part "3RP/1610G"))
    )
    (comp (ref "LINEIN-OUT")
      (value "Phoenix Pluggable 3.81mm 3 way")
      (footprint "eagle-import:3.81MM-3WAY-PLUGGABLE-SCREW")
      (libsource (lib "eagle-import") (part "CONNECTOR-M3"))
    )
    (comp (ref "PWRIN2")
      (value "Phoenix Pluggable 3.81mm 3 way")
      (footprint "eagle-import:3.81MM-3WAY-PLUGGABLE-SCREW")
      (libsource (lib "eagle-import") (part "CONNECTOR-M3"))
    )
  )
  (nets
    (net (code "1") (name "+15V") (class "Default")
      (node (ref "C16") (pin "2") (pinfunction "2_2") (pintype "passive"))
      (node (ref "C18") (pin "2") (pinfunction "2_2") (pintype "passive"))
      (node (ref "C20") (pin "2") (pinfunction "2_2") (pintype "passive"))
      (node (ref "C22") (pin "2") (pinfunction "2_2") (pintype "passive"))
      (node (ref "C24") (pin "2") (pinfunction "2_2") (pintype "passive"))
      (node (ref "C26") (pin "2") (pinfunction "2_2") (pintype "passive"))
      (node (ref "IC1") (pin "8") (pinfunction "V+_8") (pintype "power_in"))
      (node (ref "IC2") (pin "8") (pinfunction "V+_8") (pintype "power_in"))
      (node (ref "IC3") (pin "8") (pinfunction "V+_8") (pintype "power_in"))
      (node (ref "IC4") (pin "8") (pinfunction "V+_8") (pintype "power_in"))
      (node (ref "IC5") (pin "3") (pinfunction "V+_3") (pintype "power_in"))
      (node (ref "IC5") (pin "9") (pinfunction "MODE_9") (pintype "input"))
      (node (ref "IC6") (pin "8") (pinfunction "V+_8") (pintype "power_in"))
      (node (ref "IC7") (pin "8") (pinfunction "V+_8") (pintype "power_in"))
      (node (ref "LED1") (pin "A") (pinfunction "A_A") (pintype "passive"))
      (node (ref "LED10") (pin "A") (pinfunction "A_A") (pintype "passive"))
      (node (ref "LED2") (pin "A") (pinfunction "A_A") (pintype "passive"))
      (node (ref "LED3") (pin "A") (pinfunction "A_A") (pintype "passive"))
      (node (ref "LED4") (pin "A") (pinfunction "A_A") (pintype "passive"))
      (node (ref "LED5") (pin "A") (pinfunction "A_A") (pintype "passive"))
      (node (ref "LED6") (pin "A") (pinfunction "A_A") (pintype "passive"))
      (node (ref "LED7") (pin "A") (pinfunction "A_A") (pintype "passive"))
      (node (ref "LED8") (pin "A") (pinfunction "A_A") (pintype "passive"))
      (node (ref "LED9") (pin "A") (pinfunction "A_A") (pintype "passive"))
      (node (ref "PWRIN") (pin "3") (pinfunction "3_3") (pintype "bidirectional"))
      (node (ref "PWRIN1") (pin "3") (pinfunction "3_3") (pintype "bidirectional"))
      (node (ref "PWRIN2") (pin "3") (pinfunction "3_3") (pintype "bidirectional"))
      (node (ref "PWRIN3") (pin "3") (pinfunction "3_3") (pintype "bidirectional"))
      (node (ref "PWRIN4") (pin "3") (pinfunction "3_3") (pintype "bidirectional"))
      (node (ref "PWRIN5") (pin "3") (pinfunction "3_3") (pintype "bidirectional"))
      (node (ref "R29") (pin "1") (pinfunction "1_1") (pintype "passive"))
    )
    (net (code "2") (name "-15V") (class "Default")
      (node (ref "C15") (pin "2") (pinfunction "2_2") (pintype "passive"))
      (node (ref "C17") (pin "2") (pinfunction "2_2") (pintype "passive"))
      (node (ref "C19") (pin "2") (pinfunction "2_2") (pintype "passive"))
      (node (ref "C21") (pin "2") (pinfunction "2_2") (pintype "passive"))
      (node (ref "C23") (pin "2") (pinfunction "2_2") (pintype "passive"))
      (node (ref "C25") (pin "2") (pinfunction "2_2") (pintype "passive"))
      (node (ref "IC1") (pin "4") (pinfunction "V-_4") (pintype "power_in"))
      (node (ref "IC2") (pin "4") (pinfunction "V-_4") (pintype "power_in"))
      (node (ref "IC3") (pin "4") (pinfunction "V-_4") (pintype "power_in"))
      (node (ref "IC4") (pin "4") (pinfunction "V-_4") (pintype "power_in"))
      (node (ref "IC6") (pin "4") (pinfunction "V-_4") (pintype "power_in"))
      (node (ref "IC7") (pin "4") (pinfunction "V-_4") (pintype "power_in"))
      (node (ref "PWRIN") (pin "1") (pinfunction "1_1") (pintype "bidirectional"))
      (node (ref "PWRIN1") (pin "1") (pinfunction "1_1") (pintype "bidirectional"))
      (node (ref "PWRIN2") (pin "1") (pinfunction "1_1") (pintype "bidirectional"))
      (node (ref "PWRIN3") (pin "1") (pinfunction "1_1") (pintype "bidirectional"))
      (node (ref "PWRIN4") (pin "1") (pinfunction "1_1") (pintype "bidirectional"))
      (node (ref "PWRIN5") (pin "1") (pinfunction "1_1") (pintype "bidirectional"))
    )
    (net (code "3") (name "EQ-CH1") (class "Default")
      (node (ref "C14") (pin "2") (pinfunction "2_2") (pintype "passive"))
      (node (ref "IC7") (pin "1") (pinfunction "OUT_1") (pintype "output"))
      (node (ref "R38") (pin "2") (pinfunction "2_2") (pintype "passive"))
      (node (ref "R41") (pin "2") (pinfunction "2_2") (pintype "passive"))
      (node (ref "R49") (pin "1") (pinfunction "1_1") (pintype "passive"))
    )
    (net (code "4") (name "EQ-CH2") (class "Default")
      (node (ref "C11") (pin "2") (pinfunction "2_2") (pintype "passive"))
      (node (ref "IC3") (pin "1") (pinfunction "OUT_1") (pintype "output"))
      (node (ref "R34") (pin "2") (pinfunction "2_2") (pintype "passive"))
      (node (ref "R37") (pin "1") (pinfunction "1_1") (pintype "passive"))
      (node (ref "R45") (pin "2") (pinfunction "2_2") (pintype "passive"))
    )
    (net (code "5") (name "FX-BUFFER") (class "Default")
      (node (ref "C10") (pin "1") (pinfunction "1_1") (pintype "passive"))
      (node (ref "R31") (pin "1") (pinfunction "1_1") (pintype "passive"))
      (node (ref "U$1") (pin "LEFT") (pinfunction "LEFT_LEFT") (pintype "bidirectional"))
    )
    (net (code "6") (name "FXOUT1") (class "Default")
      (node (ref "FXOUT1") (pin "1") (pinfunction "1_1") (pintype "passive"))
      (node (ref "FXOUT1") (pin "3") (pinfunction "3_3") (pintype "passive"))
      (node (ref "U$1") (pin "CENTER") (pinfunction "CENTER_CENTER") (pintype "bidirectional"))
    )
    (net (code "7") (name "GND") (class "Default")
      (node (ref "C10") (pin "2") (pinfunction "2_2") (pintype "passive"))
      (node (ref "C15") (pin "1") (pinfunction "1_1") (pintype "passive"))
      (node (ref "C16") (pin "1") (pinfunction "1_1") (pintype "passive"))
      (node (ref "C17") (pin "1") (pinfunction "1_1") (pintype "passive"))
      (node (ref "C18") (pin "1") (pinfunction "1_1") (pintype "passive"))
      (node (ref "C19") (pin "1") (pinfunction "1_1") (pintype "passive"))
      (node (ref "C2") (pin "-") (pinfunction "-_-") (pintype "passive"))
      (node (ref "C20") (pin "1") (pinfunction "1_1") (pintype "passive"))
      (node (ref "C21") (pin "1") (pinfunction "1_1") (pintype "passive"))
      (node (ref "C22") (pin "1") (pinfunction "1_1") (pintype "passive"))
      (node (ref "C23") (pin "1") (pinfunction "1_1") (pintype "passive"))
      (node (ref "C24") (pin "1") (pinfunction "1_1") (pintype "passive"))
      (node (ref "C25") (pin "1") (pinfunction "1_1") (pintype "passive"))
      (node (ref "C26") (pin "1") (pinfunction "1_1") (pintype "passive"))
      (node (ref "C6") (pin "1") (pinfunction "1_1") (pintype "passive"))
      (node (ref "CON1") (pin "P$1") (pinfunction "P$1_P$1") (pintype "bidirectional"))
      (node (ref "CON1") (pin "P$2") (pinfunction "P$2_P$2") (pintype "bidirectional"))
      (node (ref "CON10") (pin "P$1") (pinfunction "P$1_P$1") (pintype "bidirectional"))
      (node (ref "CON10") (pin "P$2") (pinfunction "P$2_P$2") (pintype "bidirectional"))
      (node (ref "CON11") (pin "P$1") (pinfunction "P$1_P$1") (pintype "bidirectional"))
      (node (ref "CON11") (pin "P$2") (pinfunction "P$2_P$2") (pintype "bidirectional"))
      (node (ref "CON12") (pin "P$1") (pinfunction "P$1_P$1") (pintype "bidirectional"))
      (node (ref "CON12") (pin "P$2") (pinfunction "P$2_P$2") (pintype "bidirectional"))
      (node (ref "CON2") (pin "P$1") (pinfunction "P$1_P$1") (pintype "bidirectional"))
      (node (ref "CON2") (pin "P$2") (pinfunction "P$2_P$2") (pintype "bidirectional"))
      (node (ref "CON3") (pin "P$1") (pinfunction "P$1_P$1") (pintype "bidirectional"))
      (node (ref "CON3") (pin "P$2") (pinfunction "P$2_P$2") (pintype "bidirectional"))
      (node (ref "CON4") (pin "P$1") (pinfunction "P$1_P$1") (pintype "bidirectional"))
      (node (ref "CON4") (pin "P$2") (pinfunction "P$2_P$2") (pintype "bidirectional"))
      (node (ref "CON5") (pin "P$1") (pinfunction "P$1_P$1") (pintype "bidirectional"))
      (node (ref "CON5") (pin "P$2") (pinfunction "P$2_P$2") (pintype "bidirectional"))
      (node (ref "CON6") (pin "P$1") (pinfunction "P$1_P$1") (pintype "bidirectional"))
      (node (ref "CON6") (pin "P$2") (pinfunction "P$2_P$2") (pintype "bidirectional"))
      (node (ref "CON7") (pin "P$1") (pinfunction "P$1_P$1") (pintype "bidirectional"))
      (node (ref "CON7") (pin "P$2") (pinfunction "P$2_P$2") (pintype "bidirectional"))
      (node (ref "CON8") (pin "P$1") (pinfunction "P$1_P$1") (pintype "bidirectional"))
      (node (ref "CON8") (pin "P$2") (pinfunction "P$2_P$2") (pintype "bidirectional"))
      (node (ref "CON9") (pin "P$1") (pinfunction "P$1_P$1") (pintype "bidirectional"))
      (node (ref "CON9") (pin "P$2") (pinfunction "P$2_P$2") (pintype "bidirectional"))
      (node (ref "D1") (pin "A") (pinfunction "A_A") (pintype "passive"))
      (node (ref "EQIN") (pin "2") (pinfunction "2_2") (pintype "bidirectional"))
      (node (ref "EQOUT") (pin "2") (pinfunction "2_2") (pintype "bidirectional"))
      (node (ref "EQVOL1") (pin "1-1") (pinfunction "A_1-1") (pintype "passive"))
      (node (ref "EQVOL1") (pin "2-1") (pinfunction "A_2-1") (pintype "passive"))
      (node (ref "FADER") (pin "1") (pinfunction "A_1") (pintype "passive"))
      (node (ref "FXOUT1") (pin "2") (pinfunction "2_2") (pintype "passive"))
      (node (ref "IC5") (pin "2") (pinfunction "V-_2") (pintype "power_in"))
      (node (ref "IC5") (pin "4") (pinfunction "RLO_4") (pintype "input"))
      (node (ref "J1") (pin "SLEEVE") (pinfunction "EARTH_SLEEVE") (pintype "bidirectional"))
      (node (ref "J2") (pin "PIN") (pinfunction "PIN_PIN") (pintype "bidirectional"))
      (node (ref "J3") (pin "PIN") (pinfunction "PIN_PIN") (pintype "bidirectional"))
      (node (ref "J4") (pin "SLEEVE") (pinfunction "SLEEVE_SLEEVE") (pintype "bidirectional"))
      (node (ref "J5") (pin "SLEEVE") (pinfunction "EARTH_SLEEVE") (pintype "bidirectional"))
      (node (ref "LINE1") (pin "1-1") (pinfunction "A_1-1") (pintype "passive"))
      (node (ref "LINE1") (pin "2-1") (pinfunction "A_2-1") (pintype "passive"))
      (node (ref "LINEIN-OUT") (pin "2") (pinfunction "2_2") (pintype "bidirectional"))
      (node (ref "LINEOUT") (pin "1-1") (pinfunction "A_1-1") (pintype "passive"))
      (node (ref "LINEOUT") (pin "2-1") (pinfunction "A_2-1") (pintype "passive"))
      (node (ref "MIXER-OUT") (pin "2") (pinfunction "2_2") (pintype "passive"))
      (node (ref "MIXIN1") (pin "2") (pinfunction "2_2") (pintype "passive"))
      (node (ref "MIXIN2") (pin "2") (pinfunction "2_2") (pintype "passive"))
      (node (ref "MIXIN3") (pin "2") (pinfunction "2_2") (pintype "passive"))
      (node (ref "MIXIN4") (pin "2") (pinfunction "2_2") (pintype "passive"))
      (node (ref "MIXIN5") (pin "2") (pinfunction "2_2") (pintype "passive"))
      (node (ref "MIXIN6") (pin "2") (pinfunction "2_2") (pintype "passive"))
      (node (ref "PREAMPOUT") (pin "2") (pinfunction "2_2") (pintype "bidirectional"))
      (node (ref "PWRIN") (pin "2") (pinfunction "2_2") (pintype "bidirectional"))
      (node (ref "PWRIN1") (pin "2") (pinfunction "2_2") (pintype "bidirectional"))
      (node (ref "PWRIN2") (pin "2") (pinfunction "2_2") (pintype "bidirectional"))
      (node (ref "PWRIN3") (pin "2") (pinfunction "2_2") (pintype "bidirectional"))
      (node (ref "PWRIN4") (pin "2") (pinfunction "2_2") (pintype "bidirectional"))
      (node (ref "PWRIN5") (pin "2") (pinfunction "2_2") (pintype "bidirectional"))
      (node (ref "R1") (pin "1") (pinfunction "1_1") (pintype "passive"))
      (node (ref "R10") (pin "1") (pinfunction "1_1") (pintype "passive"))
      (node (ref "R11") (pin "2") (pinfunction "2_2") (pintype "passive"))
      (node (ref "R19") (pin "2") (pinfunction "2_2") (pintype "passive"))
      (node (ref "R27") (pin "2") (pinfunction "2_2") (pintype "passive"))
      (node (ref "R33") (pin "2") (pinfunction "2_2") (pintype "passive"))
      (node (ref "R43") (pin "2") (pinfunction "2_2") (pintype "passive"))
      (node (ref "R47") (pin "2") (pinfunction "2_2") (pintype "passive"))
      (node (ref "R48") (pin "2") (pinfunction "2_2") (pintype "passive"))
      (node (ref "R5") (pin "2") (pinfunction "2_2") (pintype "passive"))
      (node (ref "R7") (pin "2") (pinfunction "2_2") (pintype "passive"))
      (node (ref "U$5") (pin "A") (pinfunction "A_A") (pintype "passive"))
      (node (ref "U$5") (pin "S") (pinfunction "S_S") (pintype "passive"))
      (node (ref "VU-IN") (pin "2") (pinfunction "2_2") (pintype "passive"))
      (node (ref "VU-OUT") (pin "2") (pinfunction "2_2") (pintype "passive"))
    )
    (net (code "8") (name "GUITARIN1") (class "Default")
      (node (ref "C6") (pin "2") (pinfunction "2_2") (pintype "passive"))
      (node (ref "C7") (pin "2") (pinfunction "2_2") (pintype "passive"))
      (node (ref "J5") (pin "RING") (pinfunction "RING_RING") (pintype "bidirectional"))
      (node (ref "J5") (pin "TIP") (pinfunction "TIP_TIP") (pintype "bidirectional"))
      (node (ref "R27") (pin "1") (pinfunction "1_1") (pintype "passive"))
      (node (ref "U$1") (pin "RIGHT") (pinfunction "RIGHT_RIGHT") (pintype "bidirectional"))
    )
    (net (code "9") (name "LEFT-IN") (class "Default")
      (node (ref "U$2") (pin "LEFT") (pinfunction "LEFT_LEFT") (pintype "bidirectional"))
      (node (ref "VU-IN") (pin "1") (pinfunction "1_1") (pintype "passive"))
      (node (ref "VU-OUT") (pin "1") (pinfunction "1_1") (pintype "passive"))
    )
    (net (code "10") (name "LEFT-MIX") (class "Default")
      (node (ref "IC4") (pin "2") (pinfunction "-IN_2") (pintype "input"))
      (node (ref "R12") (pin "1") (pinfunction "1_1") (pintype "passive"))
      (node (ref "R13") (pin "1") (pinfunction "1_1") (pintype "passive"))
      (node (ref "R14") (pin "1") (pinfunction "1_1") (pintype "passive"))
      (node (ref "R15") (pin "1") (pinfunction "1_1") (pintype "passive"))
      (node (ref "R16") (pin "1") (pinfunction "1_1") (pintype "passive"))
      (node (ref "R17") (pin "1") (pinfunction "1_1") (pintype "passive"))
      (node (ref "R18") (pin "2") (pinfunction "2_2") (pintype "passive"))
    )
    (net (code "11") (name "LEFT1") (class "Default")
      (node (ref "MIXIN1") (pin "1") (pinfunction "1_1") (pintype "passive"))
      (node (ref "R12") (pin "2") (pinfunction "2_2") (pintype "passive"))
    )
    (net (code "12") (name "LEFT2") (class "Default")
      (node (ref "MIXIN2") (pin "1") (pinfunction "1_1") (pintype "passive"))
      (node (ref "R13") (pin "2") (pinfunction "2_2") (pintype "passive"))
    )
    (net (code "13") (name "LEFT3") (class "Default")
      (node (ref "MIXIN3") (pin "1") (pinfunction "1_1") (pintype "passive"))
      (node (ref "R14") (pin "2") (pinfunction "2_2") (pintype "passive"))
    )
    (net (code "14") (name "LEFT4") (class "Default")
      (node (ref "MIXIN4") (pin "1") (pinfunction "1_1") (pintype "passive"))
      (node (ref "R15") (pin "2") (pinfunction "2_2") (pintype "passive"))
    )
    (net (code "15") (name "LEFT5") (class "Default")
      (node (ref "MIXIN5") (pin "1") (pinfunction "1_1") (pintype "passive"))
      (node (ref "R16") (pin "2") (pinfunction "2_2") (pintype "passive"))
    )
    (net (code "16") (name "LEFT6") (class "Default")
      (node (ref "MIXIN6") (pin "1") (pinfunction "1_1") (pintype "passive"))
      (node (ref "R17") (pin "2") (pinfunction "2_2") (pintype "passive"))
    )
    (net (code "17") (name "MIC1") (class "Default")
      (node (ref "C1") (pin "+") (pinfunction "+_+") (pintype "passive"))
      (node (ref "J1") (pin "RING") (pinfunction "RING_RING") (pintype "bidirectional"))
      (node (ref "J1") (pin "TIP") (pinfunction "TIP_TIP") (pintype "bidirectional"))
    )
    (net (code "18") (name "MIX-OUT-L") (class "Default")
      (node (ref "IC4") (pin "1") (pinfunction "OUT_1") (pintype "output"))
      (node (ref "LINEOUT") (pin "1-3") (pinfunction "E_1-3") (pintype "passive"))
      (node (ref "R18") (pin "1") (pinfunction "1_1") (pintype "passive"))
    )
    (net (code "19") (name "MIX-OUT-R") (class "Default")
      (node (ref "IC4") (pin "7") (pinfunction "OUT_7") (pintype "output"))
      (node (ref "LINEOUT") (pin "2-3") (pinfunction "E_2-3") (pintype "passive"))
      (node (ref "R26") (pin "1") (pinfunction "1_1") (pintype "passive"))
    )
    (net (code "20") (name "Net-(BASS1A-A)") (class "Default")
      (node (ref "BASS1") (pin "1-1") (pinfunction "A_1-1") (pintype "passive"))
      (node (ref "C12") (pin "2") (pinfunction "2_2") (pintype "passive"))
      (node (ref "R38") (pin "1") (pinfunction "1_1") (pintype "passive"))
    )
    (net (code "21") (name "Net-(BASS1A-E)") (class "Default")
      (node (ref "BASS1") (pin "1-3") (pinfunction "E_1-3") (pintype "passive"))
      (node (ref "C12") (pin "1") (pinfunction "1_1") (pintype "passive"))
      (node (ref "R39") (pin "2") (pinfunction "2_2") (pintype "passive"))
    )
    (net (code "22") (name "Net-(BASS1A-S)") (class "Default")
      (node (ref "BASS1") (pin "1-2") (pinfunction "S_1-2") (pintype "passive"))
      (node (ref "R40") (pin "1") (pinfunction "1_1") (pintype "passive"))
    )
    (net (code "23") (name "Net-(BASS1B-A)") (class "Default")
      (node (ref "BASS1") (pin "2-1") (pinfunction "A_2-1") (pintype "passive"))
      (node (ref "C29") (pin "2") (pinfunction "2_2") (pintype "passive"))
      (node (ref "R34") (pin "1") (pinfunction "1_1") (pintype "passive"))
    )
    (net (code "24") (name "Net-(BASS1B-E)") (class "Default")
      (node (ref "BASS1") (pin "2-3") (pinfunction "E_2-3") (pintype "passive"))
      (node (ref "C29") (pin "1") (pinfunction "1_1") (pintype "passive"))
      (node (ref "R35") (pin "2") (pinfunction "2_2") (pintype "passive"))
    )
    (net (code "25") (name "Net-(BASS1B-S)") (class "Default")
      (node (ref "BASS1") (pin "2-2") (pinfunction "S_2-2") (pintype "passive"))
      (node (ref "R36") (pin "1") (pinfunction "1_1") (pintype "passive"))
    )
    (net (code "26") (name "Net-(C2-Pad+)") (class "Default")
      (node (ref "C2") (pin "+") (pinfunction "+_+") (pintype "passive"))
      (node (ref "R2") (pin "2") (pinfunction "2_2") (pintype "passive"))
    )
    (net (code "27") (name "Net-(C7-Pad1)") (class "Default")
      (node (ref "C7") (pin "1") (pinfunction "1_1") (pintype "passive"))
      (node (ref "R28") (pin "1") (pinfunction "1_1") (pintype "passive"))
    )
    (net (code "28") (name "Net-(C8-Pad2)") (class "Default")
      (node (ref "C8") (pin "2") (pinfunction "2_2") (pintype "passive"))
      (node (ref "R10") (pin "2") (pinfunction "2_2") (pintype "passive"))
    )
    (net (code "29") (name "Net-(D1-PadC)") (class "Default")
      (node (ref "D1") (pin "C") (pinfunction "C_C") (pintype "passive"))
      (node (ref "D2") (pin "C") (pinfunction "C_C") (pintype "passive"))
    )
    (net (code "30") (name "Net-(EQIN-Pad1)") (class "Default")
      (node (ref "EQIN") (pin "1") (pinfunction "1_1") (pintype "bidirectional"))
      (node (ref "R44") (pin "2") (pinfunction "2_2") (pintype "passive"))
    )
    (net (code "31") (name "Net-(EQIN-Pad3)") (class "Default")
      (node (ref "EQIN") (pin "3") (pinfunction "3_3") (pintype "bidirectional"))
      (node (ref "R32") (pin "2") (pinfunction "2_2") (pintype "passive"))
    )
    (net (code "32") (name "Net-(EQVOL1A-E)") (class "Default")
      (node (ref "EQVOL1") (pin "1-3") (pinfunction "E_1-3") (pintype "passive"))
      (node (ref "IC7") (pin "7") (pinfunction "OUT_7") (pintype "output"))
      (node (ref "R39") (pin "1") (pinfunction "1_1") (pintype "passive"))
      (node (ref "R42") (pin "1") (pinfunction "1_1") (pintype "passive"))
    )
    (net (code "33") (name "Net-(EQVOL1A-S)") (class "Default")
      (node (ref "EQOUT") (pin "1") (pinfunction "1_1") (pintype "bidirectional"))
      (node (ref "EQVOL1") (pin "1-2") (pinfunction "S_1-2") (pintype "passive"))
    )
    (net (code "34") (name "Net-(EQVOL1B-E)") (class "Default")
      (node (ref "EQVOL1") (pin "2-3") (pinfunction "E_2-3") (pintype "passive"))
      (node (ref "IC3") (pin "7") (pinfunction "OUT_7") (pintype "output"))
      (node (ref "R35") (pin "1") (pinfunction "1_1") (pintype "passive"))
      (node (ref "R46") (pin "1") (pinfunction "1_1") (pintype "passive"))
    )
    (net (code "35") (name "Net-(EQVOL1B-S)") (class "Default")
      (node (ref "EQOUT") (pin "3") (pinfunction "3_3") (pintype "bidirectional"))
      (node (ref "EQVOL1") (pin "2-2") (pinfunction "S_2-2") (pintype "passive"))
    )
    (net (code "36") (name "Net-(FADER-E)") (class "Default")
      (node (ref "C4") (pin "2") (pinfunction "2_2") (pintype "passive"))
      (node (ref "FADER") (pin "3") (pinfunction "E_3") (pintype "passive"))
      (node (ref "GAIN1") (pin "2") (pinfunction "S_2") (pintype "passive"))
      (node (ref "IC1") (pin "7") (pinfunction "OUT_7") (pintype "output"))
    )
    (net (code "37") (name "Net-(FADER-S)") (class "Default")
      (node (ref "FADER") (pin "2") (pinfunction "S_2") (pintype "passive"))
      (node (ref "R6") (pin "2") (pinfunction "2_2") (pintype "passive"))
    )
    (net (code "38") (name "Net-(FXGAIN-A)") (class "Default")
      (node (ref "FXGAIN") (pin "1") (pinfunction "A_1") (pintype "passive"))
      (node (ref "R30") (pin "1") (pinfunction "1_1") (pintype "passive"))
    )
    (net (code "39") (name "Net-(FXGAIN-S)") (class "Default")
      (node (ref "C9") (pin "2") (pinfunction "2_2") (pintype "passive"))
      (node (ref "FXGAIN") (pin "2") (pinfunction "S_2") (pintype "passive"))
      (node (ref "IC6") (pin "1") (pinfunction "OUT_1") (pintype "output"))
      (node (ref "LED11") (pin "A") (pinfunction "A_A") (pintype "passive"))
      (node (ref "LED12") (pin "K") (pinfunction "C_K") (pintype "passive"))
      (node (ref "R31") (pin "2") (pinfunction "2_2") (pintype "passive"))
    )
    (net (code "40") (name "Net-(GAIN1-A)") (class "Default")
      (node (ref "C4") (pin "1") (pinfunction "1_1") (pintype "passive"))
      (node (ref "GAIN1") (pin "1") (pinfunction "A_1") (pintype "passive"))
      (node (ref "IC1") (pin "6") (pinfunction "-IN_6") (pintype "input"))
      (node (ref "R4") (pin "1") (pinfunction "1_1") (pintype "passive"))
    )
    (net (code "41") (name "Net-(IC1A-+IN)") (class "Default")
      (node (ref "C1") (pin "-") (pinfunction "-_-") (pintype "passive"))
      (node (ref "D2") (pin "A") (pinfunction "A_A") (pintype "passive"))
      (node (ref "IC1") (pin "3") (pinfunction "+IN_3") (pintype "input"))
      (node (ref "R1") (pin "2") (pinfunction "2_2") (pintype "passive"))
    )
    (net (code "42") (name "Net-(IC1A--IN)") (class "Default")
      (node (ref "C3") (pin "1") (pinfunction "1_1") (pintype "passive"))
      (node (ref "IC1") (pin "2") (pinfunction "-IN_2") (pintype "input"))
      (node (ref "R2") (pin "1") (pinfunction "1_1") (pintype "passive"))
      (node (ref "R3") (pin "2") (pinfunction "2_2") (pintype "passive"))
    )
    (net (code "43") (name "Net-(IC1A-OUT)") (class "Default")
      (node (ref "C3") (pin "2") (pinfunction "2_2") (pintype "passive"))
      (node (ref "IC1") (pin "1") (pinfunction "OUT_1") (pintype "output"))
      (node (ref "R3") (pin "1") (pinfunction "1_1") (pintype "passive"))
      (node (ref "R4") (pin "2") (pinfunction "2_2") (pintype "passive"))
    )
    (net (code "44") (name "Net-(IC1B-+IN)") (class "Default")
      (node (ref "IC1") (pin "5") (pinfunction "+IN_5") (pintype "input"))
      (node (ref "R5") (pin "1") (pinfunction "1_1") (pintype "passive"))
    )
    (net (code "45") (name "Net-(IC2A-+IN)") (class "Default")
      (node (ref "IC2") (pin "3") (pinfunction "+IN_3") (pintype "input"))
      (node (ref "R7") (pin "1") (pinfunction "1_1") (pintype "passive"))
    )
    (net (code "46") (name "Net-(IC2A--IN)") (class "Default")
      (node (ref "C5") (pin "1") (pinfunction "1_1") (pintype "passive"))
      (node (ref "IC2") (pin "2") (pinfunction "-IN_2") (pintype "input"))
      (node (ref "R6") (pin "1") (pinfunction "1_1") (pintype "passive"))
      (node (ref "R8") (pin "2") (pinfunction "2_2") (pintype "passive"))
    )
    (net (code "47") (name "Net-(IC3A-+IN)") (class "Default")
      (node (ref "IC3") (pin "3") (pinfunction "+IN_3") (pintype "input"))
      (node (ref "R33") (pin "1") (pinfunction "1_1") (pintype "passive"))
    )
    (net (code "48") (name "Net-(IC3A--IN)") (class "Default")
      (node (ref "C11") (pin "1") (pinfunction "1_1") (pintype "passive"))
      (node (ref "IC3") (pin "2") (pinfunction "-IN_2") (pintype "input"))
      (node (ref "R32") (pin "1") (pinfunction "1_1") (pintype "passive"))
      (node (ref "R37") (pin "2") (pinfunction "2_2") (pintype "passive"))
    )
    (net (code "49") (name "Net-(IC3B-+IN)") (class "Default")
      (node (ref "IC3") (pin "5") (pinfunction "+IN_5") (pintype "input"))
      (node (ref "R47") (pin "1") (pinfunction "1_1") (pintype "passive"))
    )
    (net (code "50") (name "Net-(IC3B--IN)") (class "Default")
      (node (ref "C30") (pin "2") (pinfunction "2_2") (pintype "passive"))
      (node (ref "IC3") (pin "6") (pinfunction "-IN_6") (pintype "input"))
      (node (ref "R36") (pin "2") (pinfunction "2_2") (pintype "passive"))
    )
    (net (code "51") (name "Net-(IC4A-+IN)") (class "Default")
      (node (ref "IC4") (pin "3") (pinfunction "+IN_3") (pintype "input"))
      (node (ref "R11") (pin "1") (pinfunction "1_1") (pintype "passive"))
    )
    (net (code "52") (name "Net-(IC4B-+IN)") (class "Default")
      (node (ref "IC4") (pin "5") (pinfunction "+IN_5") (pintype "input"))
      (node (ref "R19") (pin "1") (pinfunction "1_1") (pintype "passive"))
    )
    (net (code "53") (name "Net-(IC5-LED1)") (class "Default")
      (node (ref "IC5") (pin "1") (pinfunction "LED1_1") (pintype "output"))
      (node (ref "LED1") (pin "K") (pinfunction "C_K") (pintype "passive"))
    )
    (net (code "54") (name "Net-(IC5-LED2)") (class "Default")
      (node (ref "IC5") (pin "18") (pinfunction "LED2_18") (pintype "output"))
      (node (ref "LED2") (pin "K") (pinfunction "C_K") (pintype "passive"))
    )
    (net (code "55") (name "Net-(IC5-LED3)") (class "Default")
      (node (ref "IC5") (pin "17") (pinfunction "LED3_17") (pintype "output"))
      (node (ref "LED3") (pin "K") (pinfunction "C_K") (pintype "passive"))
    )
    (net (code "56") (name "Net-(IC5-LED4)") (class "Default")
      (node (ref "IC5") (pin "16") (pinfunction "LED4_16") (pintype "output"))
      (node (ref "LED4") (pin "K") (pinfunction "C_K") (pintype "passive"))
    )
    (net (code "57") (name "Net-(IC5-LED5)") (class "Default")
      (node (ref "IC5") (pin "15") (pinfunction "LED5_15") (pintype "output"))
      (node (ref "LED5") (pin "K") (pinfunction "C_K") (pintype "passive"))
    )
    (net (code "58") (name "Net-(IC5-LED6)") (class "Default")
      (node (ref "IC5") (pin "14") (pinfunction "LED6_14") (pintype "output"))
      (node (ref "LED6") (pin "K") (pinfunction "C_K") (pintype "passive"))
    )
    (net (code "59") (name "Net-(IC5-LED7)") (class "Default")
      (node (ref "IC5") (pin "13") (pinfunction "LED7_13") (pintype "output"))
      (node (ref "LED7") (pin "K") (pinfunction "C_K") (pintype "passive"))
    )
    (net (code "60") (name "Net-(IC5-LED8)") (class "Default")
      (node (ref "IC5") (pin "12") (pinfunction "LED8_12") (pintype "output"))
      (node (ref "LED8") (pin "K") (pinfunction "C_K") (pintype "passive"))
    )
    (net (code "61") (name "Net-(IC5-LED9)") (class "Default")
      (node (ref "IC5") (pin "11") (pinfunction "LED9_11") (pintype "output"))
      (node (ref "LED9") (pin "K") (pinfunction "C_K") (pintype "passive"))
    )
    (net (code "62") (name "Net-(IC5-LED10)") (class "Default")
      (node (ref "IC5") (pin "10") (pinfunction "LED10_10") (pintype "output"))
      (node (ref "LED10") (pin "K") (pinfunction "C_K") (pintype "passive"))
    )
    (net (code "63") (name "Net-(IC5-REFADJ)") (class "Default")
      (node (ref "IC5") (pin "8") (pinfunction "REFADJ_8") (pintype "passive"))
      (node (ref "R9") (pin "1") (pinfunction "1_1") (pintype "passive"))
      (node (ref "U$5") (pin "E") (pinfunction "E_E") (pintype "passive"))
    )
    (net (code "64") (name "Net-(IC5-REFOUT)") (class "Default")
      (node (ref "IC5") (pin "6") (pinfunction "RHI_6") (pintype "input"))
      (node (ref "IC5") (pin "7") (pinfunction "REFOUT_7") (pintype "output"))
      (node (ref "R9") (pin "2") (pinfunction "2_2") (pintype "passive"))
    )
    (net (code "65") (name "Net-(IC6A-+IN)") (class "Default")
      (node (ref "IC6") (pin "3") (pinfunction "+IN_3") (pintype "input"))
      (node (ref "R28") (pin "2") (pinfunction "2_2") (pintype "passive"))
      (node (ref "R29") (pin "2") (pinfunction "2_2") (pintype "passive"))
    )
    (net (code "66") (name "Net-(IC6A--IN)") (class "Default")
      (node (ref "C8") (pin "1") (pinfunction "1_1") (pintype "passive"))
      (node (ref "C9") (pin "1") (pinfunction "1_1") (pintype "passive"))
      (node (ref "IC6") (pin "2") (pinfunction "-IN_2") (pintype "input"))
      (node (ref "LED11") (pin "K") (pinfunction "C_K") (pintype "passive"))
      (node (ref "LED12") (pin "A") (pinfunction "A_A") (pintype "passive"))
      (node (ref "R30") (pin "2") (pinfunction "2_2") (pintype "passive"))
    )
    (net (code "67") (name "Net-(IC7A-+IN)") (class "Default")
      (node (ref "IC7") (pin "3") (pinfunction "+IN_3") (pintype "input"))
      (node (ref "R48") (pin "1") (pinfunction "1_1") (pintype "passive"))
    )
    (net (code "68") (name "Net-(IC7A--IN)") (class "Default")
      (node (ref "C14") (pin "1") (pinfunction "1_1") (pintype "passive"))
      (node (ref "IC7") (pin "2") (pinfunction "-IN_2") (pintype "input"))
      (node (ref "R44") (pin "1") (pinfunction "1_1") (pintype "passive"))
      (node (ref "R49") (pin "2") (pinfunction "2_2") (pintype "passive"))
    )
    (net (code "69") (name "Net-(IC7B-+IN)") (class "Default")
      (node (ref "IC7") (pin "5") (pinfunction "+IN_5") (pintype "input"))
      (node (ref "R43") (pin "1") (pinfunction "1_1") (pintype "passive"))
    )
    (net (code "70") (name "Net-(IC7B--IN)") (class "Default")
      (node (ref "C13") (pin "2") (pinfunction "2_2") (pintype "passive"))
      (node (ref "IC7") (pin "6") (pinfunction "-IN_6") (pintype "input"))
      (node (ref "R40") (pin "2") (pinfunction "2_2") (pintype "passive"))
    )
    (net (code "71") (name "Net-(LINE1A-E)") (class "Default")
      (node (ref "J2") (pin "SHELL") (pinfunction "SHELL_SHELL") (pintype "bidirectional"))
      (node (ref "J4") (pin "RING") (pinfunction "RING_RING") (pintype "bidirectional"))
      (node (ref "LINE1") (pin "1-3") (pinfunction "E_1-3") (pintype "passive"))
    )
    (net (code "72") (name "Net-(LINE1A-S)") (class "Default")
      (node (ref "LINE1") (pin "1-2") (pinfunction "S_1-2") (pintype "passive"))
      (node (ref "LINEIN-OUT") (pin "1") (pinfunction "1_1") (pintype "bidirectional"))
    )
    (net (code "73") (name "Net-(LINE1B-E)") (class "Default")
      (node (ref "J3") (pin "SHELL") (pinfunction "SHELL_SHELL") (pintype "bidirectional"))
      (node (ref "J4") (pin "TIP") (pinfunction "TIP_TIP") (pintype "bidirectional"))
      (node (ref "LINE1") (pin "2-3") (pinfunction "E_2-3") (pintype "passive"))
    )
    (net (code "74") (name "Net-(LINE1B-S)") (class "Default")
      (node (ref "LINE1") (pin "2-2") (pinfunction "S_2-2") (pintype "passive"))
      (node (ref "LINEIN-OUT") (pin "3") (pinfunction "3_3") (pintype "bidirectional"))
    )
    (net (code "75") (name "Net-(LINEOUTA-S)") (class "Default")
      (node (ref "LINEOUT") (pin "1-2") (pinfunction "S_1-2") (pintype "passive"))
      (node (ref "MIXER-OUT") (pin "3") (pinfunction "3_3") (pintype "passive"))
    )
    (net (code "76") (name "Net-(LINEOUTB-S)") (class "Default")
      (node (ref "LINEOUT") (pin "2-2") (pinfunction "S_2-2") (pintype "passive"))
      (node (ref "MIXER-OUT") (pin "1") (pinfunction "1_1") (pintype "passive"))
    )
    (net (code "77") (name "Net-(TREB1A-A)") (class "Default")
      (node (ref "R41") (pin "1") (pinfunction "1_1") (pintype "passive"))
      (node (ref "TREB1") (pin "1-1") (pinfunction "A_1-1") (pintype "passive"))
    )
    (net (code "78") (name "Net-(TREB1A-E)") (class "Default")
      (node (ref "R42") (pin "2") (pinfunction "2_2") (pintype "passive"))
      (node (ref "TREB1") (pin "1-3") (pinfunction "E_1-3") (pintype "passive"))
    )
    (net (code "79") (name "Net-(TREB1A-S)") (class "Default")
      (node (ref "C13") (pin "1") (pinfunction "1_1") (pintype "passive"))
      (node (ref "TREB1") (pin "1-2") (pinfunction "S_1-2") (pintype "passive"))
    )
    (net (code "80") (name "Net-(TREB1B-A)") (class "Default")
      (node (ref "R45") (pin "1") (pinfunction "1_1") (pintype "passive"))
      (node (ref "TREB1") (pin "2-1") (pinfunction "A_2-1") (pintype "passive"))
    )
    (net (code "81") (name "Net-(TREB1B-E)") (class "Default")
      (node (ref "R46") (pin "2") (pinfunction "2_2") (pintype "passive"))
      (node (ref "TREB1") (pin "2-3") (pinfunction "E_2-3") (pintype "passive"))
    )
    (net (code "82") (name "Net-(TREB1B-S)") (class "Default")
      (node (ref "C30") (pin "1") (pinfunction "1_1") (pintype "passive"))
      (node (ref "TREB1") (pin "2-2") (pinfunction "S_2-2") (pintype "passive"))
    )
    (net (code "83") (name "PREAMP1") (class "Default")
      (node (ref "C5") (pin "2") (pinfunction "2_2") (pintype "passive"))
      (node (ref "IC2") (pin "1") (pinfunction "OUT_1") (pintype "output"))
      (node (ref "PREAMPOUT") (pin "1") (pinfunction "1_1") (pintype "bidirectional"))
      (node (ref "PREAMPOUT") (pin "3") (pinfunction "3_3") (pintype "bidirectional"))
      (node (ref "R8") (pin "1") (pinfunction "1_1") (pintype "passive"))
    )
    (net (code "84") (name "RIGHT-IN") (class "Default")
      (node (ref "U$2") (pin "RIGHT") (pinfunction "RIGHT_RIGHT") (pintype "bidirectional"))
      (node (ref "VU-IN") (pin "3") (pinfunction "3_3") (pintype "passive"))
      (node (ref "VU-OUT") (pin "3") (pinfunction "3_3") (pintype "passive"))
    )
    (net (code "85") (name "RIGHT-MIX") (class "Default")
      (node (ref "IC4") (pin "6") (pinfunction "-IN_6") (pintype "input"))
      (node (ref "R20") (pin "1") (pinfunction "1_1") (pintype "passive"))
      (node (ref "R21") (pin "1") (pinfunction "1_1") (pintype "passive"))
      (node (ref "R22") (pin "1") (pinfunction "1_1") (pintype "passive"))
      (node (ref "R23") (pin "1") (pinfunction "1_1") (pintype "passive"))
      (node (ref "R24") (pin "1") (pinfunction "1_1") (pintype "passive"))
      (node (ref "R25") (pin "1") (pinfunction "1_1") (pintype "passive"))
      (node (ref "R26") (pin "2") (pinfunction "2_2") (pintype "passive"))
    )
    (net (code "86") (name "RIGHT1") (class "Default")
      (node (ref "MIXIN1") (pin "3") (pinfunction "3_3") (pintype "passive"))
      (node (ref "R20") (pin "2") (pinfunction "2_2") (pintype "passive"))
    )
    (net (code "87") (name "RIGHT2") (class "Default")
      (node (ref "MIXIN2") (pin "3") (pinfunction "3_3") (pintype "passive"))
      (node (ref "R21") (pin "2") (pinfunction "2_2") (pintype "passive"))
    )
    (net (code "88") (name "RIGHT3") (class "Default")
      (node (ref "MIXIN3") (pin "3") (pinfunction "3_3") (pintype "passive"))
      (node (ref "R22") (pin "2") (pinfunction "2_2") (pintype "passive"))
    )
    (net (code "89") (name "RIGHT4") (class "Default")
      (node (ref "MIXIN4") (pin "3") (pinfunction "3_3") (pintype "passive"))
      (node (ref "R23") (pin "2") (pinfunction "2_2") (pintype "passive"))
    )
    (net (code "90") (name "RIGHT5") (class "Default")
      (node (ref "MIXIN5") (pin "3") (pinfunction "3_3") (pintype "passive"))
      (node (ref "R24") (pin "2") (pinfunction "2_2") (pintype "passive"))
    )
    (net (code "91") (name "RIGHT6") (class "Default")
      (node (ref "MIXIN6") (pin "3") (pinfunction "3_3") (pintype "passive"))
      (node (ref "R25") (pin "2") (pinfunction "2_2") (pintype "passive"))
    )
    (net (code "92") (name "SIG") (class "Default")
      (node (ref "IC5") (pin "5") (pinfunction "SIGIN_5") (pintype "input"))
      (node (ref "U$2") (pin "CENTER") (pinfunction "CENTER_CENTER") (pintype "bidirectional"))
    )
    (net (code "93") (name "unconnected-(CON1-PadP$3)") (class "Default")
      (node (ref "CON1") (pin "P$3") (pinfunction "P$3_P$3") (pintype "bidirectional"))
    )
    (net (code "94") (name "unconnected-(CON1-PadP$4)") (class "Default")
      (node (ref "CON1") (pin "P$4") (pinfunction "P$4_P$4") (pintype "bidirectional"))
    )
    (net (code "95") (name "unconnected-(CON2-PadP$3)") (class "Default")
      (node (ref "CON2") (pin "P$3") (pinfunction "P$3_P$3") (pintype "bidirectional"))
    )
    (net (code "96") (name "unconnected-(CON2-PadP$4)") (class "Default")
      (node (ref "CON2") (pin "P$4") (pinfunction "P$4_P$4") (pintype "bidirectional"))
    )
    (net (code "97") (name "unconnected-(CON3-PadP$3)") (class "Default")
      (node (ref "CON3") (pin "P$3") (pinfunction "P$3_P$3") (pintype "bidirectional"))
    )
    (net (code "98") (name "unconnected-(CON3-PadP$4)") (class "Default")
      (node (ref "CON3") (pin "P$4") (pinfunction "P$4_P$4") (pintype "bidirectional"))
    )
    (net (code "99") (name "unconnected-(CON4-PadP$3)") (class "Default")
      (node (ref "CON4") (pin "P$3") (pinfunction "P$3_P$3") (pintype "bidirectional"))
    )
    (net (code "100") (name "unconnected-(CON4-PadP$4)") (class "Default")
      (node (ref "CON4") (pin "P$4") (pinfunction "P$4_P$4") (pintype "bidirectional"))
    )
    (net (code "101") (name "unconnected-(CON5-PadP$3)") (class "Default")
      (node (ref "CON5") (pin "P$3") (pinfunction "P$3_P$3") (pintype "bidirectional"))
    )
    (net (code "102") (name "unconnected-(CON5-PadP$4)") (class "Default")
      (node (ref "CON5") (pin "P$4") (pinfunction "P$4_P$4") (pintype "bidirectional"))
    )
    (net (code "103") (name "unconnected-(CON6-PadP$3)") (class "Default")
      (node (ref "CON6") (pin "P$3") (pinfunction "P$3_P$3") (pintype "bidirectional"))
    )
    (net (code "104") (name "unconnected-(CON6-PadP$4)") (class "Default")
      (node (ref "CON6") (pin "P$4") (pinfunction "P$4_P$4") (pintype "bidirectional"))
    )
    (net (code "105") (name "unconnected-(CON7-PadP$3)") (class "Default")
      (node (ref "CON7") (pin "P$3") (pinfunction "P$3_P$3") (pintype "bidirectional"))
    )
    (net (code "106") (name "unconnected-(CON7-PadP$4)") (class "Default")
      (node (ref "CON7") (pin "P$4") (pinfunction "P$4_P$4") (pintype "bidirectional"))
    )
    (net (code "107") (name "unconnected-(CON8-PadP$3)") (class "Default")
      (node (ref "CON8") (pin "P$3") (pinfunction "P$3_P$3") (pintype "bidirectional"))
    )
    (net (code "108") (name "unconnected-(CON8-PadP$4)") (class "Default")
      (node (ref "CON8") (pin "P$4") (pinfunction "P$4_P$4") (pintype "bidirectional"))
    )
    (net (code "109") (name "unconnected-(CON9-PadP$3)") (class "Default")
      (node (ref "CON9") (pin "P$3") (pinfunction "P$3_P$3") (pintype "bidirectional"))
    )
    (net (code "110") (name "unconnected-(CON9-PadP$4)") (class "Default")
      (node (ref "CON9") (pin "P$4") (pinfunction "P$4_P$4") (pintype "bidirectional"))
    )
    (net (code "111") (name "unconnected-(CON10-PadP$3)") (class "Default")
      (node (ref "CON10") (pin "P$3") (pinfunction "P$3_P$3") (pintype "bidirectional"))
    )
    (net (code "112") (name "unconnected-(CON10-PadP$4)") (class "Default")
      (node (ref "CON10") (pin "P$4") (pinfunction "P$4_P$4") (pintype "bidirectional"))
    )
    (net (code "113") (name "unconnected-(CON11-PadP$3)") (class "Default")
      (node (ref "CON11") (pin "P$3") (pinfunction "P$3_P$3") (pintype "bidirectional"))
    )
    (net (code "114") (name "unconnected-(CON11-PadP$4)") (class "Default")
      (node (ref "CON11") (pin "P$4") (pinfunction "P$4_P$4") (pintype "bidirectional"))
    )
    (net (code "115") (name "unconnected-(CON12-PadP$3)") (class "Default")
      (node (ref "CON12") (pin "P$3") (pinfunction "P$3_P$3") (pintype "bidirectional"))
    )
    (net (code "116") (name "unconnected-(CON12-PadP$4)") (class "Default")
      (node (ref "CON12") (pin "P$4") (pinfunction "P$4_P$4") (pintype "bidirectional"))
    )
    (net (code "117") (name "unconnected-(FXGAIN-E-Pad3)") (class "Default")
      (node (ref "FXGAIN") (pin "3") (pinfunction "E_3") (pintype "passive"))
    )
    (net (code "118") (name "unconnected-(GAIN1-E-Pad3)") (class "Default")
      (node (ref "GAIN1") (pin "3") (pinfunction "E_3") (pintype "passive"))
    )
    (net (code "119") (name "unconnected-(IC6B-+IN-Pad5)") (class "Default")
      (node (ref "IC6") (pin "5") (pinfunction "+IN_5") (pintype "input"))
    )
    (net (code "120") (name "unconnected-(IC6B--IN-Pad6)") (class "Default")
      (node (ref "IC6") (pin "6") (pinfunction "-IN_6") (pintype "input"))
    )
    (net (code "121") (name "unconnected-(IC6B-OUT-Pad7)") (class "Default")
      (node (ref "IC6") (pin "7") (pinfunction "OUT_7") (pintype "output"))
    )
    (net (code "122") (name "unconnected-(J1-EARTH-NORM-PadSLEEVE-NORM)") (class "Default")
      (node (ref "J1") (pin "SLEEVE-NORM") (pinfunction "EARTH-NORM_SLEEVE-NORM") (pintype "bidirectional"))
    )
    (net (code "123") (name "unconnected-(J1-PadRING-NORM)") (class "Default")
      (node (ref "J1") (pin "RING-NORM") (pinfunction "RING-NORM_RING-NORM") (pintype "bidirectional"))
    )
    (net (code "124") (name "unconnected-(J1-PadTIP-NORM)") (class "Default")
      (node (ref "J1") (pin "TIP-NORM") (pinfunction "TIP-NORM_TIP-NORM") (pintype "bidirectional"))
    )
    (net (code "125") (name "unconnected-(J2-PadSWITCH)") (class "Default")
      (node (ref "J2") (pin "SWITCH") (pinfunction "SWITCH_SWITCH") (pintype "bidirectional"))
    )
    (net (code "126") (name "unconnected-(J3-PadSWITCH)") (class "Default")
      (node (ref "J3") (pin "SWITCH") (pinfunction "SWITCH_SWITCH") (pintype "bidirectional"))
    )
    (net (code "127") (name "unconnected-(J4-PadRSH)") (class "Default")
      (node (ref "J4") (pin "RSH") (pinfunction "RSH_RSH") (pintype "bidirectional"))
    )
    (net (code "128") (name "unconnected-(J4-PadTSH)") (class "Default")
      (node (ref "J4") (pin "TSH") (pinfunction "TSH_TSH") (pintype "bidirectional"))
    )
    (net (code "129") (name "unconnected-(J5-EARTH-NORM-PadSLEEVE-NORM)") (class "Default")
      (node (ref "J5") (pin "SLEEVE-NORM") (pinfunction "EARTH-NORM_SLEEVE-NORM") (pintype "bidirectional"))
    )
    (net (code "130") (name "unconnected-(J5-PadRING-NORM)") (class "Default")
      (node (ref "J5") (pin "RING-NORM") (pinfunction "RING-NORM_RING-NORM") (pintype "bidirectional"))
    )
    (net (code "131") (name "unconnected-(J5-PadTIP-NORM)") (class "Default")
      (node (ref "J5") (pin "TIP-NORM") (pinfunction "TIP-NORM_TIP-NORM") (pintype "bidirectional"))
    )
  )
)
